# Car_board.net
KiCad netlist of a schematic drawn in Altium Designer
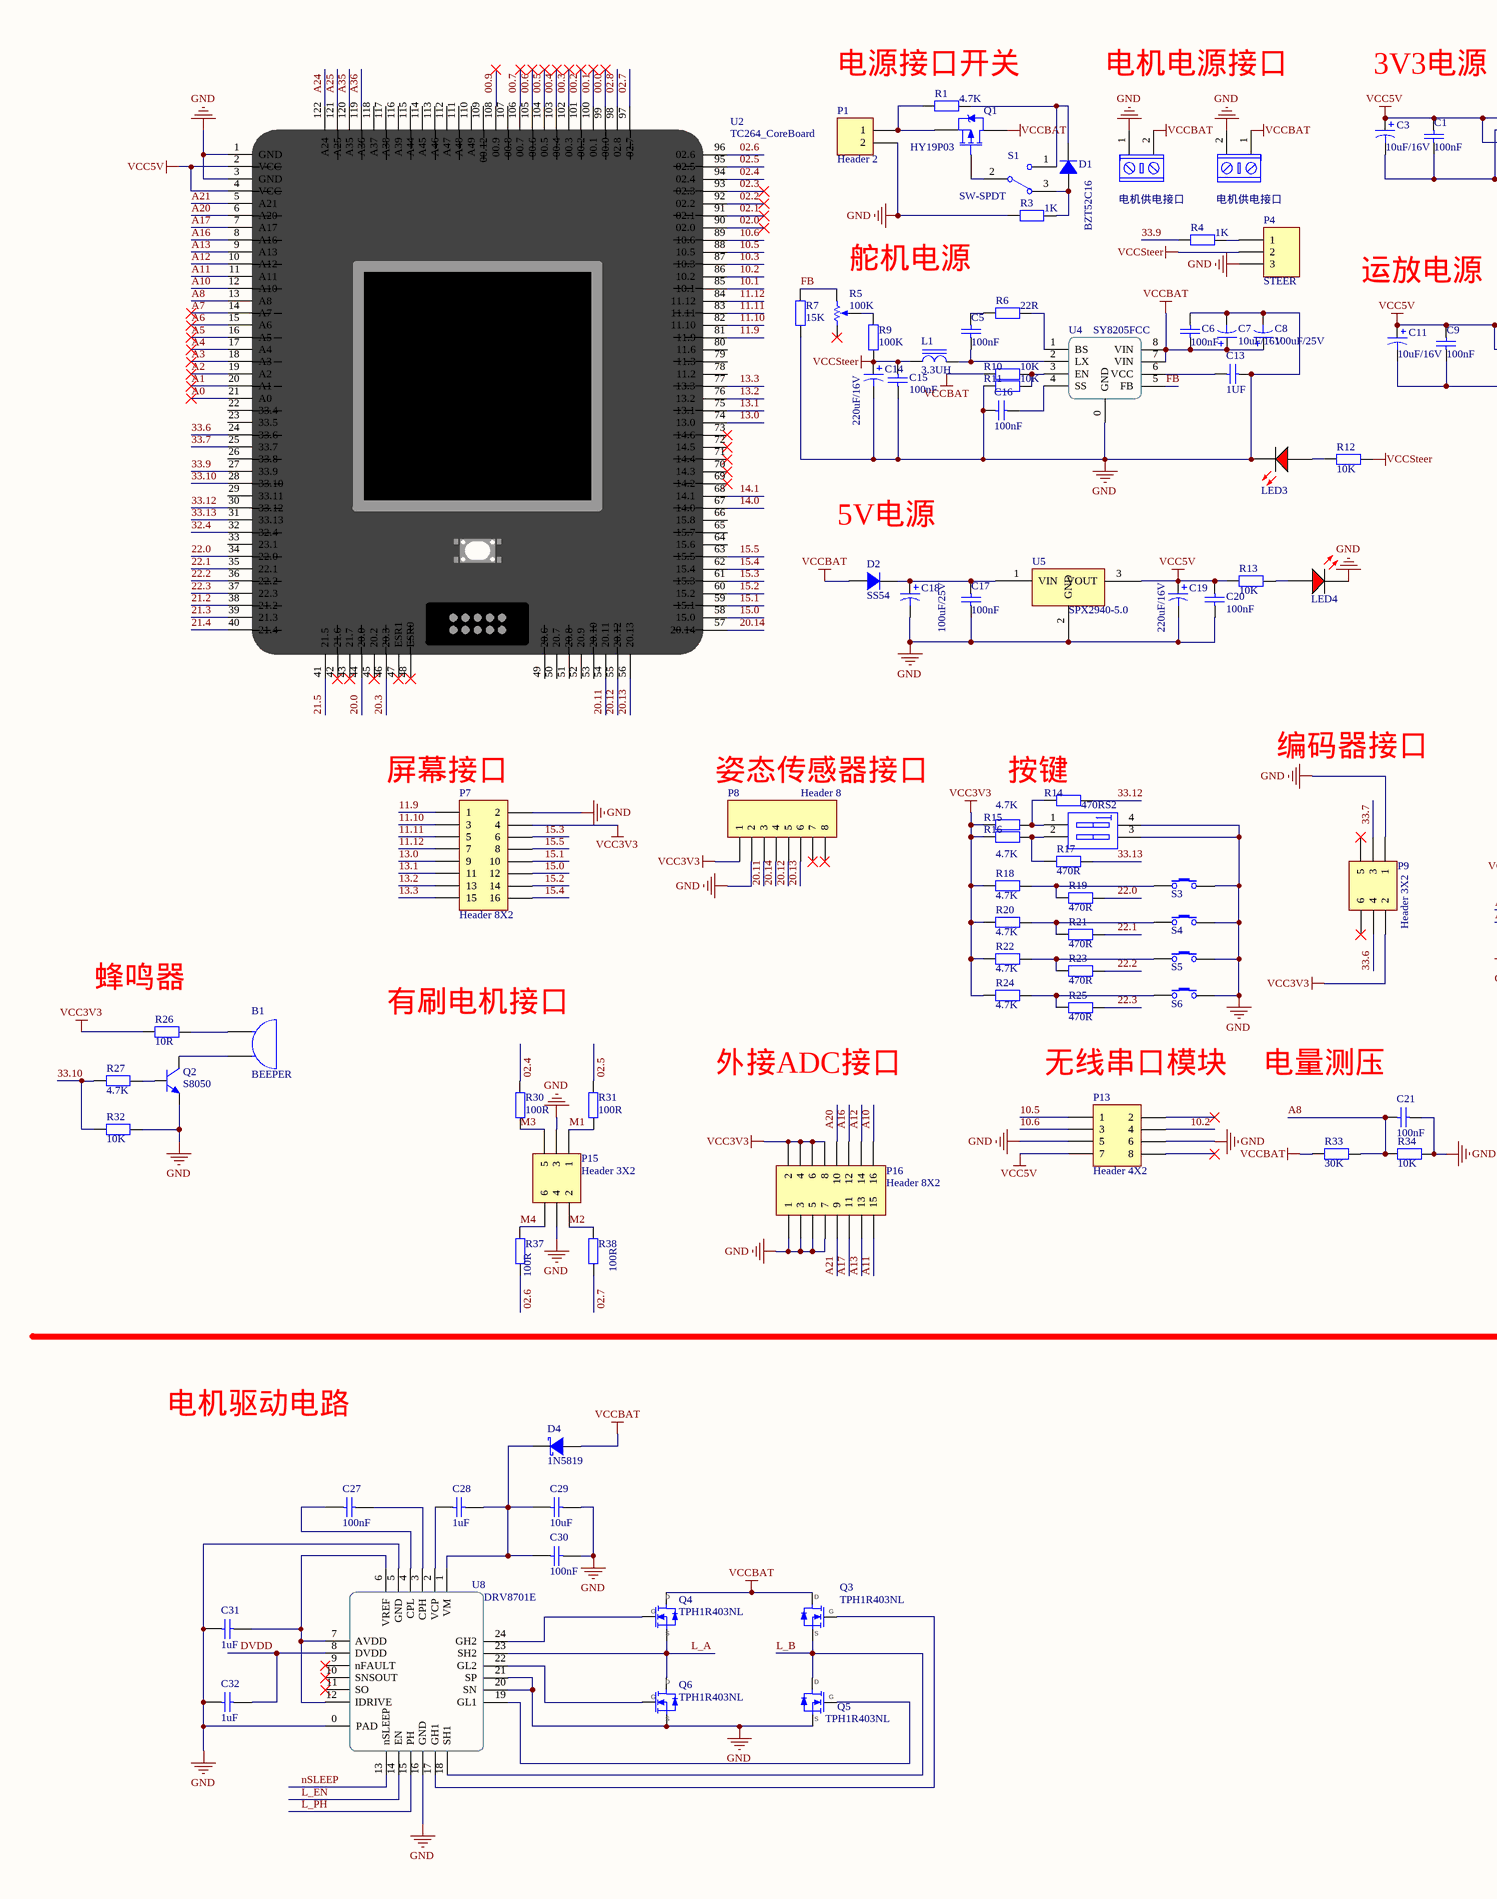
[diagram p0: Car_board.SchDoc, left]
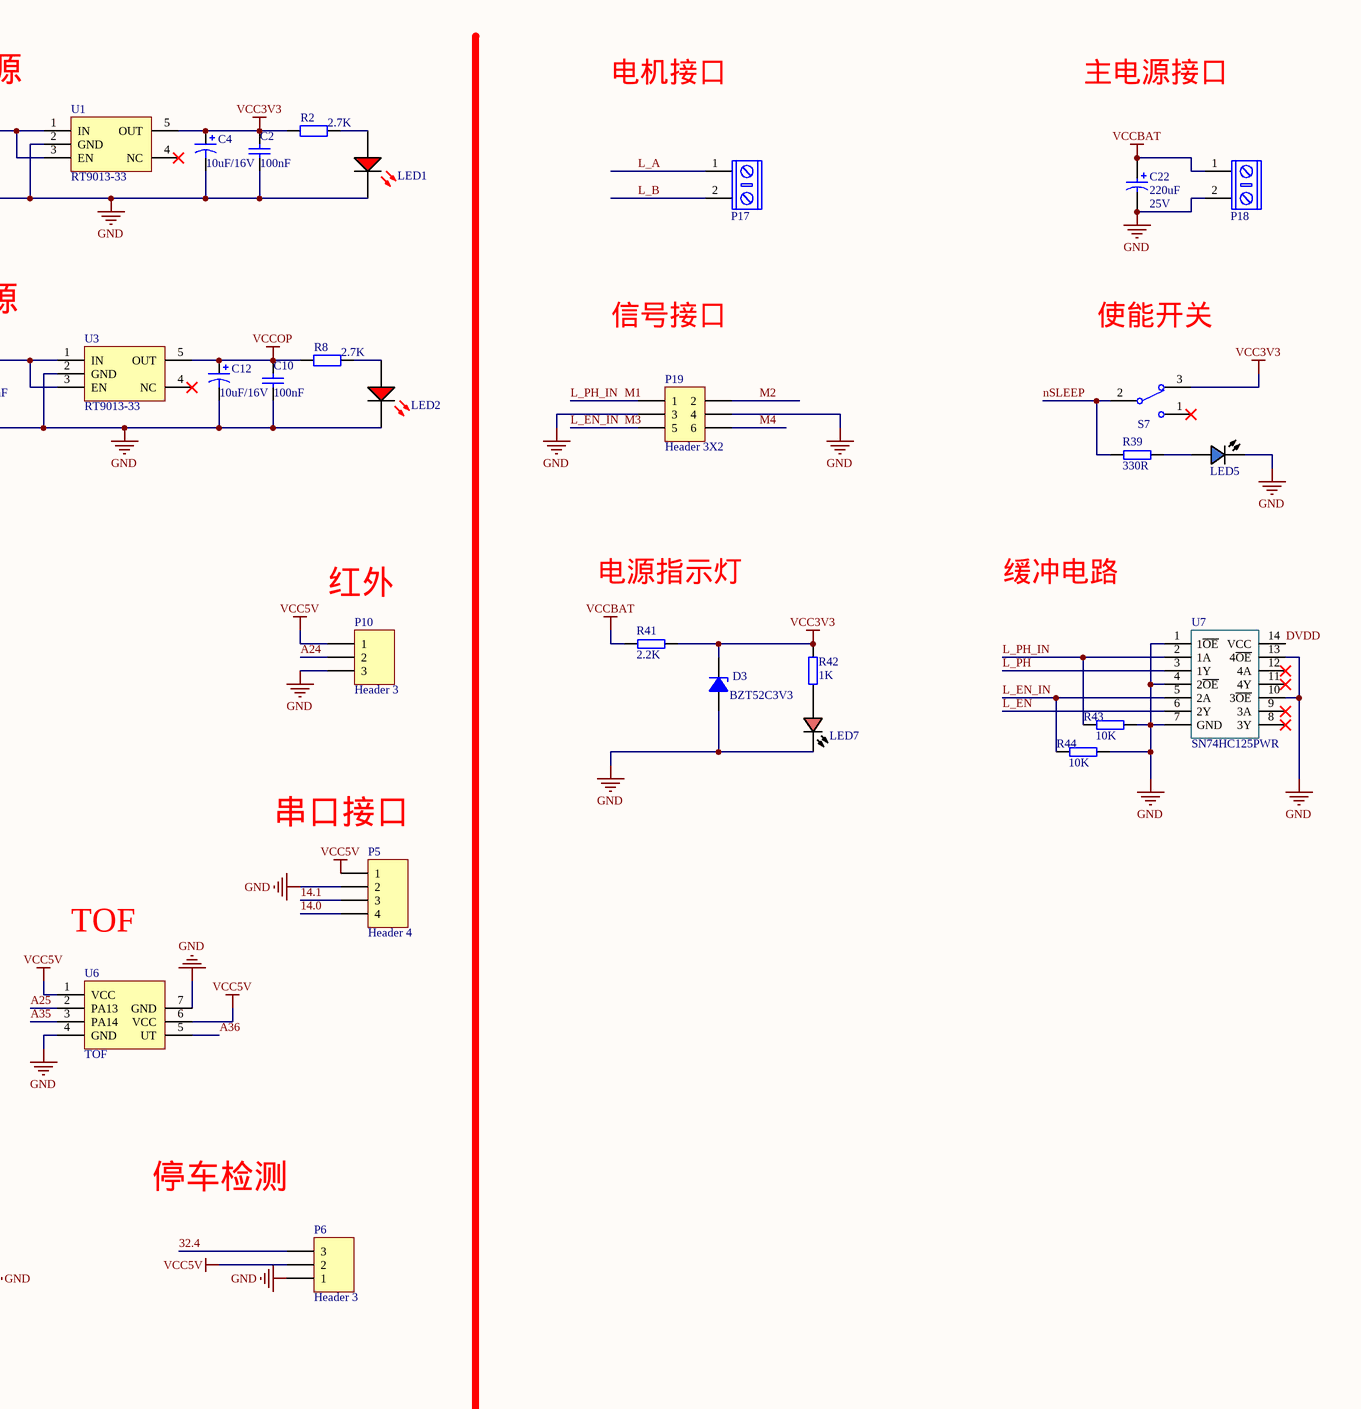
[diagram p1: Car_board.SchDoc, right]

(export (version "E")
  (design (tool "Eeschema 10.0.6"))
  (components
    (comp (ref "B1")
      (value "BEEPER")
      (footprint "BEEPER")
      (description "3V蜂鸣器")
      (libsource (lib "AMRP_XXX") (part "BUZZER"))
    )
    (comp (ref "C1")
      (value "100nF")
      (footprint "0603C")
      (description "电容")
      (fields (field (name "Comment") "Cap") (field (name "PUBLISHER") "Altium Limited"))
      (libsource (lib "AMRP_XXX") (part "Cap"))
    )
    (comp (ref "C2")
      (value "100nF")
      (footprint "0603C")
      (description "电容")
      (fields (field (name "Comment") "Cap") (field (name "PUBLISHER") "Altium Limited"))
      (libsource (lib "AMRP_XXX") (part "Cap"))
    )
    (comp (ref "C3")
      (value "10uF/16V")
      (footprint "3216")
      (description "钽电解电容/16V/A型封装")
      (fields (field (name "Comment") "Cap Pol2") (field (name "PUBLISHER") "Altium Limited"))
      (libsource (lib "AMRP_XXX") (part "Cap Pol2"))
    )
    (comp (ref "C4")
      (value "10uF/16V")
      (footprint "3216")
      (description "钽电解电容/16V/A型封装")
      (fields (field (name "Comment") "Cap Pol2") (field (name "PUBLISHER") "Altium Limited"))
      (libsource (lib "AMRP_XXX") (part "Cap Pol2"))
    )
    (comp (ref "C5")
      (value "100nF")
      (footprint "0603C")
      (description "电容")
      (fields (field (name "Comment") "Cap") (field (name "PUBLISHER") "Altium Limited"))
      (libsource (lib "AMRP_XXX") (part "Cap"))
    )
    (comp (ref "C6")
      (value "100nF")
      (footprint "0603C")
      (description "电容")
      (fields (field (name "Comment") "Cap") (field (name "PUBLISHER") "Altium Limited"))
      (libsource (lib "AMRP_XXX") (part "Cap"))
    )
    (comp (ref "C7")
      (value "10uF/16V")
      (footprint "3216")
      (description "钽电解电容/16V/A型封装")
      (fields (field (name "Comment") "Cap Pol2") (field (name "PUBLISHER") "Altium Limited"))
      (libsource (lib "AMRP_XXX") (part "Cap Pol2"))
    )
    (comp (ref "C8")
      (value "100uF/25V")
      (footprint "CAPSO_6.3*7.7")
      (description "钽电解电容/16V/A型封装")
      (fields (field (name "Comment") "Cap Pol2") (field (name "PUBLISHER") "Altium Limited"))
      (libsource (lib "AMRP_XXX") (part "Cap Pol2"))
    )
    (comp (ref "C9")
      (value "100nF")
      (footprint "0603C")
      (description "电容")
      (fields (field (name "Comment") "Cap") (field (name "PUBLISHER") "Altium Limited"))
      (libsource (lib "AMRP_XXX") (part "Cap"))
    )
    (comp (ref "C10")
      (value "100nF")
      (footprint "0603C")
      (description "电容")
      (fields (field (name "Comment") "Cap") (field (name "PUBLISHER") "Altium Limited"))
      (libsource (lib "AMRP_XXX") (part "Cap"))
    )
    (comp (ref "C11")
      (value "10uF/16V")
      (footprint "3216")
      (description "钽电解电容/16V/A型封装")
      (fields (field (name "Comment") "Cap Pol2") (field (name "PUBLISHER") "Altium Limited"))
      (libsource (lib "AMRP_XXX") (part "Cap Pol2"))
    )
    (comp (ref "C12")
      (value "10uF/16V")
      (footprint "3216")
      (description "钽电解电容/16V/A型封装")
      (fields (field (name "Comment") "Cap Pol2") (field (name "PUBLISHER") "Altium Limited"))
      (libsource (lib "AMRP_XXX") (part "Cap Pol2"))
    )
    (comp (ref "C13")
      (value "1UF")
      (footprint "0603C")
      (description "电容")
      (fields (field (name "Comment") "Cap") (field (name "PUBLISHER") "Altium Limited"))
      (libsource (lib "AMRP_XXX") (part "Cap"))
    )
    (comp (ref "C14")
      (value "220uF/16V")
      (footprint "CAPSO_6.3*7.7")
      (description "钽电解电容/16V/A型封装")
      (fields (field (name "Comment") "Cap Pol2") (field (name "PUBLISHER") "Altium Limited"))
      (libsource (lib "AMRP_XXX") (part "Cap Pol2"))
    )
    (comp (ref "C15")
      (value "100nF")
      (footprint "0603C")
      (description "电容")
      (fields (field (name "Comment") "Cap") (field (name "PUBLISHER") "Altium Limited"))
      (libsource (lib "AMRP_XXX") (part "Cap"))
    )
    (comp (ref "C16")
      (value "100nF")
      (footprint "0603C")
      (description "电容")
      (fields (field (name "Comment") "Cap") (field (name "PUBLISHER") "Altium Limited"))
      (libsource (lib "AMRP_XXX") (part "Cap"))
    )
    (comp (ref "C17")
      (value "100nF")
      (footprint "0603C")
      (description "电容")
      (fields (field (name "Comment") "Cap") (field (name "PUBLISHER") "Altium Limited"))
      (libsource (lib "AMRP_XXX") (part "Cap"))
    )
    (comp (ref "C18")
      (value "100uF/25V")
      (footprint "CAPSO_6.3*7.7")
      (description "钽电解电容/16V/A型封装")
      (fields (field (name "Comment") "Cap Pol2") (field (name "PUBLISHER") "Altium Limited"))
      (libsource (lib "AMRP_XXX") (part "Cap Pol2"))
    )
    (comp (ref "C19")
      (value "220uF/16V")
      (footprint "CAPSO_6.3*7.7")
      (description "钽电解电容/16V/A型封装")
      (fields (field (name "Comment") "Cap Pol2") (field (name "PUBLISHER") "Altium Limited"))
      (libsource (lib "AMRP_XXX") (part "Cap Pol2"))
    )
    (comp (ref "C20")
      (value "100nF")
      (footprint "0603C")
      (description "电容")
      (fields (field (name "Comment") "Cap") (field (name "PUBLISHER") "Altium Limited"))
      (libsource (lib "AMRP_XXX") (part "Cap"))
    )
    (comp (ref "C21")
      (value "100nF")
      (footprint "0603C")
      (description "电容")
      (fields (field (name "Comment") "Cap") (field (name "PUBLISHER") "Altium Limited"))
      (libsource (lib "AMRP_XXX") (part "Cap"))
    )
    (comp (ref "C22")
      (value "220uF")
      (footprint "CAPPR3.5-8X11.5")
      (description "Polarized Capacitor (Radial)")
      (fields
        (field (name "VOLTAGE") "25V")
        (field (name "Comment") "220uF 25V")
        (field (name "PUBLISHER") "Altium Limited")
      )
      (libsource (lib "DRV8701_DualMotorDriver") (part "Cap-Elect"))
    )
    (comp (ref "C27")
      (value "100nF")
      (footprint "CAPC1608[0603]S-N")
      (description "贴片电容")
      (fields
        (field (name "VOLTAGE") "50V")
        (field (name "TOLERANCE") "±10%")
        (field (name "PUBLISHER") "Altium Limited")
      )
      (libsource (lib "DRV8701_DualMotorDriver") (part "Cap-Chip_1"))
    )
    (comp (ref "C28")
      (value "1uF")
      (footprint "CAPC1608[0603]S-N")
      (description "贴片电容")
      (fields
        (field (name "VOLTAGE") "25V")
        (field (name "TOLERANCE") "±10%")
        (field (name "PUBLISHER") "Altium Limited")
      )
      (libsource (lib "DRV8701_DualMotorDriver") (part "Cap-Chip_2"))
    )
    (comp (ref "C29")
      (value "10uF")
      (footprint "CAPC2012[0805]S-N")
      (description "贴片电容")
      (fields
        (field (name "VOLTAGE") "25V")
        (field (name "TOLERANCE") "±10%")
        (field (name "PUBLISHER") "Altium Limited")
      )
      (libsource (lib "DRV8701_DualMotorDriver") (part "Cap-Chip"))
    )
    (comp (ref "C30")
      (value "100nF")
      (footprint "CAPC1608[0603]S-N")
      (description "贴片电容")
      (fields
        (field (name "VOLTAGE") "50V")
        (field (name "TOLERANCE") "±10%")
        (field (name "PUBLISHER") "Altium Limited")
      )
      (libsource (lib "DRV8701_DualMotorDriver") (part "Cap-Chip_1"))
    )
    (comp (ref "C31")
      (value "1uF")
      (footprint "CAPC1608[0603]S-N")
      (description "贴片电容")
      (fields
        (field (name "VOLTAGE") "25V")
        (field (name "TOLERANCE") "±10%")
        (field (name "PUBLISHER") "Altium Limited")
      )
      (libsource (lib "DRV8701_DualMotorDriver") (part "Cap-Chip_2"))
    )
    (comp (ref "C32")
      (value "1uF")
      (footprint "CAPC1608[0603]S-N")
      (description "贴片电容")
      (fields
        (field (name "VOLTAGE") "25V")
        (field (name "TOLERANCE") "±10%")
        (field (name "PUBLISHER") "Altium Limited")
      )
      (libsource (lib "DRV8701_DualMotorDriver") (part "Cap-Chip_2"))
    )
    (comp (ref "D1")
      (value "BZT52C16")
      (footprint "SOD-123")
      (description "TVS二极管 Diode")
      (fields (field (name "PUBLISHER") "Altium Limited"))
      (libsource (lib "TVS") (part "TVS"))
    )
    (comp (ref "D2")
      (value "SS54")
      (footprint "SOD-123")
      (description "TVS二极管 Diode")
      (fields (field (name "PUBLISHER") "Altium Limited"))
      (libsource (lib "TVS") (part "TVS"))
    )
    (comp (ref "D3")
      (value "BZT52C3V3")
      (footprint "SOD-123-L")
      (description "3.3V稳压二极管 SOD-123")
      (fields (field (name "PUBLISHER") "Altium Limited"))
      (libsource (lib "DRV8701_DualMotorDriver") (part "Diode Zen"))
    )
    (comp (ref "D4")
      (value "1N5819")
      (footprint "SOD-123-L")
      (description "肖特基二极管 Diode")
      (fields (field (name "PARTNUMBER") "1N5819") (field (name "PUBLISHER") "Altium Limited"))
      (libsource (lib "DRV8701_DualMotorDriver") (part "Diode Schottky"))
    )
    (comp (ref "L1")
      (value "3.3UH")
      (footprint "L-0630")
      (description "Power Inductor, Ferrite-Core")
      (fields (field (name "PUBLISHER") "Altium Limited"))
      (libsource (lib "工字电感") (part "Ind-Power"))
    )
    (comp (ref "LED1")
      (value "LED 3R")
      (footprint "0805D")
      (description "Red, Typical INFRARED GaAs LED")
      (fields (field (name "PUBLISHER") "Altium Limited"))
      (libsource (lib "直插LED5MM") (part "LED DIP Red"))
    )
    (comp (ref "LED2")
      (value "LED 3R")
      (footprint "0805D")
      (description "Red, Typical INFRARED GaAs LED")
      (fields (field (name "PUBLISHER") "Altium Limited"))
      (libsource (lib "直插LED5MM") (part "LED DIP Red"))
    )
    (comp (ref "LED3")
      (value "LED 3R")
      (footprint "0805D")
      (description "Red, Typical INFRARED GaAs LED")
      (fields (field (name "PUBLISHER") "Altium Limited"))
      (libsource (lib "直插LED5MM") (part "LED DIP Red"))
    )
    (comp (ref "LED4")
      (value "LED 3R")
      (footprint "0805D")
      (description "Red, Typical INFRARED GaAs LED")
      (fields (field (name "PUBLISHER") "Altium Limited"))
      (libsource (lib "直插LED5MM") (part "LED DIP Red"))
    )
    (comp (ref "LED5")
      (value "Blue")
      (footprint "LEDC1608(0603)")
      (description "Typical Chip LED")
      (fields (field (name "PUBLISHER") "Altium Limited"))
      (libsource (lib "DRV8701_DualMotorDriver") (part "LED Chip Blue"))
    )
    (comp (ref "LED7")
      (value "~")
      (footprint "LEDC1608(0603)")
      (description "Typical Chip LED")
      (fields (field (name "PUBLISHER") "Altium Limited"))
      (libsource (lib "DRV8701_DualMotorDriver") (part "LED Chip Red"))
    )
    (comp (ref "P1")
      (value "Header 2")
      (footprint "PCBComponent_1")
      (description "Header, 2-Pin")
      (fields (field (name "PUBLISHER") "Altium Limited"))
      (libsource (lib "Miscellaneous Connectors") (part "Header 2"))
    )
    (comp (ref "P2")
      (value "电机供电接口")
      (footprint "KF/WJ/DG 301-2p-5.0mm")
      (description "接线端子 2Pin")
      (libsource (lib "接线端子") (part "KF/WJ/DG 30x"))
    )
    (comp (ref "P3")
      (value "电机供电接口")
      (footprint "KF/WJ/DG 301-2p-5.0mm")
      (description "接线端子 2Pin")
      (libsource (lib "接线端子") (part "KF/WJ/DG 30x"))
    )
    (comp (ref "P4")
      (value "STEER")
      (footprint "HDR1X3")
      (description "Header, 3-Pin")
      (fields (field (name "PUBLISHER") "Altium Limited"))
      (libsource (lib "Miscellaneous Connectors") (part "Header 3"))
    )
    (comp (ref "P5")
      (value "Header 4")
      (footprint "HDR1X4")
      (description "Header, 4-Pin")
      (fields (field (name "PUBLISHER") "Altium Limited"))
      (libsource (lib "Miscellaneous Connectors") (part "Header 4"))
    )
    (comp (ref "P6")
      (value "Header 3")
      (footprint "HDR1X3")
      (description "Header, 3-Pin")
      (fields (field (name "PUBLISHER") "Altium Limited"))
      (libsource (lib "") (part "Header 3_1"))
    )
    (comp (ref "P7")
      (value "Header 8X2")
      (footprint "HDR2X8")
      (description "Header, 8-Pin, Dual row")
      (fields (field (name "PUBLISHER") "Altium Limited"))
      (libsource (lib "Miscellaneous Connectors") (part "Header 8X2"))
    )
    (comp (ref "P8")
      (value "Header 8")
      (footprint "HDR1X8")
      (description "Header, 8-Pin")
      (fields (field (name "PUBLISHER") "Altium Limited"))
      (libsource (lib "Miscellaneous Connectors") (part "Header 8"))
    )
    (comp (ref "P9")
      (value "Header 3X2")
      (footprint "HDR2X3")
      (description "Header, 3-Pin, Dual row")
      (fields (field (name "PUBLISHER") "Altium Limited"))
      (libsource (lib "Miscellaneous Connectors") (part "Header 3X2"))
    )
    (comp (ref "P10")
      (value "Header 3")
      (footprint "HDR1X3")
      (description "Header, 3-Pin")
      (fields (field (name "PUBLISHER") "Altium Limited"))
      (libsource (lib "Miscellaneous Connectors") (part "Header 3"))
    )
    (comp (ref "P13")
      (value "Header 4X2")
      (footprint "HDR2X4")
      (description "Header, 4-Pin, Dual row")
      (fields (field (name "PUBLISHER") "Altium Limited"))
      (libsource (lib "Miscellaneous Connectors") (part "Header 4X2"))
    )
    (comp (ref "P15")
      (value "Header 3X2")
      (footprint "HDR2X3")
      (description "Header, 3-Pin, Dual row")
      (fields (field (name "PUBLISHER") "Altium Limited"))
      (libsource (lib "Miscellaneous Connectors") (part "Header 3X2"))
    )
    (comp (ref "P16")
      (value "Header 8X2")
      (footprint "HDR2X8")
      (description "Header, 8-Pin, Dual row")
      (fields (field (name "PUBLISHER") "Altium Limited"))
      (libsource (lib "") (part "Header 8X2_1"))
    )
    (comp (ref "P17")
      (value "KF/WJ/DG 30x connecter")
      (footprint "KF/WJ/DG 301-2p-5.0mm")
      (description "接线端子 2Pin")
      (libsource (lib "DRV8701_DualMotorDriver") (part "KF/WJ/DG 30x"))
    )
    (comp (ref "P18")
      (value "KF/WJ/DG 30x connecter")
      (footprint "KF/WJ/DG 301-2p-5.0mm")
      (description "接线端子 2Pin")
      (libsource (lib "DRV8701_DualMotorDriver") (part "KF/WJ/DG 30x"))
    )
    (comp (ref "P19")
      (value "Header 3X2")
      (footprint "HDR2X3")
      (description "Header, 3-Pin, Dual row")
      (fields (field (name "PUBLISHER") "Altium Limited"))
      (libsource (lib "DRV8701_DualMotorDriver") (part "Header 3X2"))
    )
    (comp (ref "Q1")
      (value "HY19P03")
      (footprint "TO-252")
      (description "P-Channel Power MOSFET")
      (fields (field (name "PUBLISHER") "Altium Limited"))
      (libsource (lib "Miscellaneous Devices") (part "PMOS-2"))
    )
    (comp (ref "Q2")
      (value "S8050")
      (footprint "SOT-23")
      (description "Discrete NPN Bipolar Transistor")
      (fields (field (name "PARTNUMBER") "S8050") (field (name "PUBLISHER") "Altium Limited"))
      (libsource (lib "S8050") (part "NPN S8050"))
    )
    (comp (ref "Q3")
      (value "TPH1R403NL")
      (footprint "DFN5x6")
      (description "东芝 N沟 MOS")
      (libsource (lib "DRV8701_DualMotorDriver") (part "TPH1R403NL"))
    )
    (comp (ref "Q4")
      (value "TPH1R403NL")
      (footprint "DFN5x6")
      (description "东芝 N沟 MOS")
      (libsource (lib "DRV8701_DualMotorDriver") (part "TPH1R403NL"))
    )
    (comp (ref "Q5")
      (value "TPH1R403NL")
      (footprint "DFN5x6")
      (description "东芝 N沟 MOS")
      (libsource (lib "DRV8701_DualMotorDriver") (part "TPH1R403NL"))
    )
    (comp (ref "Q6")
      (value "TPH1R403NL")
      (footprint "DFN5x6")
      (description "东芝 N沟 MOS")
      (libsource (lib "DRV8701_DualMotorDriver") (part "TPH1R403NL"))
    )
    (comp (ref "R1")
      (value "4.7K")
      (footprint "0603R")
      (description "电阻")
      (fields (field (name "Comment") "Res2") (field (name "PUBLISHER") "Altium Limited"))
      (libsource (lib "") (part "Res2_2"))
    )
    (comp (ref "R2")
      (value "2.7K")
      (footprint "0603R")
      (description "电阻")
      (fields (field (name "Comment") "Res2") (field (name "PUBLISHER") "Altium Limited"))
      (libsource (lib "AMRP_XXX") (part "Res2"))
    )
    (comp (ref "R3")
      (value "1K")
      (footprint "0603R")
      (description "电阻")
      (fields (field (name "Comment") "Res2") (field (name "PUBLISHER") "Altium Limited"))
      (libsource (lib "") (part "Res2_2"))
    )
    (comp (ref "R4")
      (value "1K")
      (footprint "0603R")
      (description "电阻")
      (fields (field (name "Comment") "Res2") (field (name "PUBLISHER") "Altium Limited"))
      (libsource (lib "AMRP_XXX") (part "Res2"))
    )
    (comp (ref "R5")
      (value "100K")
      (footprint "VR5_N")
      (description "精密电位器")
      (fields (field (name "Comment") "RPot") (field (name "PUBLISHER") "Altium Limited"))
      (libsource (lib "AMRP_XXX") (part "RPot"))
    )
    (comp (ref "R6")
      (value "22R")
      (footprint "0603R")
      (description "电阻")
      (fields (field (name "Comment") "Res2") (field (name "PUBLISHER") "Altium Limited"))
      (libsource (lib "AMRP_XXX") (part "Res2"))
    )
    (comp (ref "R7")
      (value "15K")
      (footprint "0603R")
      (description "电阻")
      (fields (field (name "Comment") "Res2") (field (name "PUBLISHER") "Altium Limited"))
      (libsource (lib "") (part "Res2_3"))
    )
    (comp (ref "R8")
      (value "2.7K")
      (footprint "0603R")
      (description "电阻")
      (fields (field (name "Comment") "Res2") (field (name "PUBLISHER") "Altium Limited"))
      (libsource (lib "AMRP_XXX") (part "Res2"))
    )
    (comp (ref "R9")
      (value "100K")
      (footprint "0603R")
      (description "电阻")
      (fields (field (name "Comment") "Res2") (field (name "PUBLISHER") "Altium Limited"))
      (libsource (lib "") (part "Res2_3"))
    )
    (comp (ref "R10")
      (value "10K")
      (footprint "0603R")
      (description "电阻")
      (fields (field (name "Comment") "Res2") (field (name "PUBLISHER") "Altium Limited"))
      (libsource (lib "AMRP_XXX") (part "Res2"))
    )
    (comp (ref "R11")
      (value "10K")
      (footprint "0603R")
      (description "电阻")
      (fields (field (name "Comment") "Res2") (field (name "PUBLISHER") "Altium Limited"))
      (libsource (lib "AMRP_XXX") (part "Res2"))
    )
    (comp (ref "R12")
      (value "10K")
      (footprint "0603R")
      (description "电阻")
      (fields (field (name "Comment") "Res2") (field (name "PUBLISHER") "Altium Limited"))
      (libsource (lib "AMRP_XXX") (part "Res2"))
    )
    (comp (ref "R13")
      (value "10K")
      (footprint "0603R")
      (description "电阻")
      (fields (field (name "Comment") "Res2") (field (name "PUBLISHER") "Altium Limited"))
      (libsource (lib "") (part "Res2_2"))
    )
    (comp (ref "R14")
      (value "470R")
      (footprint "0603R")
      (description "电阻")
      (fields (field (name "Comment") "Res2") (field (name "PUBLISHER") "Altium Limited"))
      (libsource (lib "") (part "Res2_2"))
    )
    (comp (ref "R15")
      (value "4.7K")
      (footprint "0603R")
      (description "电阻")
      (fields (field (name "Comment") "Res2") (field (name "PUBLISHER") "Altium Limited"))
      (libsource (lib "") (part "Res2_2"))
    )
    (comp (ref "R16")
      (value "4.7K")
      (footprint "0603R")
      (description "电阻")
      (fields (field (name "Comment") "Res2") (field (name "PUBLISHER") "Altium Limited"))
      (libsource (lib "") (part "Res2_2"))
    )
    (comp (ref "R17")
      (value "470R")
      (footprint "0603R")
      (description "电阻")
      (fields (field (name "Comment") "Res2") (field (name "PUBLISHER") "Altium Limited"))
      (libsource (lib "") (part "Res2_2"))
    )
    (comp (ref "R18")
      (value "4.7K")
      (footprint "0603R")
      (description "电阻")
      (fields (field (name "Comment") "Res2") (field (name "PUBLISHER") "Altium Limited"))
      (libsource (lib "") (part "Res2_2"))
    )
    (comp (ref "R19")
      (value "470R")
      (footprint "0603R")
      (description "电阻")
      (fields (field (name "Comment") "Res2") (field (name "PUBLISHER") "Altium Limited"))
      (libsource (lib "") (part "Res2_2"))
    )
    (comp (ref "R20")
      (value "4.7K")
      (footprint "0603R")
      (description "电阻")
      (fields (field (name "Comment") "Res2") (field (name "PUBLISHER") "Altium Limited"))
      (libsource (lib "") (part "Res2_2"))
    )
    (comp (ref "R21")
      (value "470R")
      (footprint "0603R")
      (description "电阻")
      (fields (field (name "Comment") "Res2") (field (name "PUBLISHER") "Altium Limited"))
      (libsource (lib "") (part "Res2_2"))
    )
    (comp (ref "R22")
      (value "4.7K")
      (footprint "0603R")
      (description "电阻")
      (fields (field (name "Comment") "Res2") (field (name "PUBLISHER") "Altium Limited"))
      (libsource (lib "") (part "Res2_2"))
    )
    (comp (ref "R23")
      (value "470R")
      (footprint "0603R")
      (description "电阻")
      (fields (field (name "Comment") "Res2") (field (name "PUBLISHER") "Altium Limited"))
      (libsource (lib "") (part "Res2_2"))
    )
    (comp (ref "R24")
      (value "4.7K")
      (footprint "0603R")
      (description "电阻")
      (fields (field (name "Comment") "Res2") (field (name "PUBLISHER") "Altium Limited"))
      (libsource (lib "") (part "Res2_2"))
    )
    (comp (ref "R25")
      (value "470R")
      (footprint "0603R")
      (description "电阻")
      (fields (field (name "Comment") "Res2") (field (name "PUBLISHER") "Altium Limited"))
      (libsource (lib "") (part "Res2_2"))
    )
    (comp (ref "R26")
      (value "10R")
      (footprint "0603R")
      (description "电阻")
      (fields (field (name "Comment") "Res2") (field (name "PUBLISHER") "Altium Limited"))
      (libsource (lib "") (part "Res2_2"))
    )
    (comp (ref "R27")
      (value "4.7K")
      (footprint "0603R")
      (description "电阻")
      (fields (field (name "Comment") "Res2") (field (name "PUBLISHER") "Altium Limited"))
      (libsource (lib "") (part "Res2_2"))
    )
    (comp (ref "R30")
      (value "100R")
      (footprint "0603R")
      (description "电阻")
      (fields (field (name "Comment") "Res2") (field (name "PUBLISHER") "Altium Limited"))
      (libsource (lib "") (part "Res2_1"))
    )
    (comp (ref "R31")
      (value "100R")
      (footprint "0603R")
      (description "电阻")
      (fields (field (name "Comment") "Res2") (field (name "PUBLISHER") "Altium Limited"))
      (libsource (lib "") (part "Res2_1"))
    )
    (comp (ref "R32")
      (value "10K")
      (footprint "0603R")
      (description "电阻")
      (fields (field (name "Comment") "Res2") (field (name "PUBLISHER") "Altium Limited"))
      (libsource (lib "") (part "Res2_2"))
    )
    (comp (ref "R33")
      (value "30K")
      (footprint "0603R")
      (description "电阻")
      (fields (field (name "Comment") "Res2") (field (name "PUBLISHER") "Altium Limited"))
      (libsource (lib "") (part "Res2_2"))
    )
    (comp (ref "R34")
      (value "10K")
      (footprint "0603R")
      (description "电阻")
      (fields (field (name "Comment") "Res2") (field (name "PUBLISHER") "Altium Limited"))
      (libsource (lib "") (part "Res2_2"))
    )
    (comp (ref "R37")
      (value "100R")
      (footprint "0603R")
      (description "电阻")
      (fields (field (name "Comment") "Res2") (field (name "PUBLISHER") "Altium Limited"))
      (libsource (lib "") (part "Res2_1"))
    )
    (comp (ref "R38")
      (value "100R")
      (footprint "0603R")
      (description "电阻")
      (fields (field (name "Comment") "Res2") (field (name "PUBLISHER") "Altium Limited"))
      (libsource (lib "") (part "Res2_1"))
    )
    (comp (ref "R39")
      (value "330R")
      (footprint "RESC1608[0603]S-N")
      (description "贴片电阻")
      (fields
        (field (name "TOLERANCE") "±1%")
        (field (name "Comment") "330R ±1%")
        (field (name "PUBLISHER") "Altium Limited")
      )
      (libsource (lib "DRV8701_DualMotorDriver") (part "Res-Chip_3"))
    )
    (comp (ref "R41")
      (value "2.2K")
      (footprint "RESC1608[0603]S-N")
      (description "贴片电阻")
      (fields
        (field (name "TOLERANCE") "±1%")
        (field (name "Comment") "2.2K ±1%")
        (field (name "PUBLISHER") "Altium Limited")
      )
      (libsource (lib "DRV8701_DualMotorDriver") (part "Res-Chip"))
    )
    (comp (ref "R42")
      (value "1K")
      (footprint "RESC1608[0603]S-N")
      (description "贴片电阻")
      (fields
        (field (name "TOLERANCE") "±1%")
        (field (name "Comment") "1K ±1%")
        (field (name "PUBLISHER") "Altium Limited")
      )
      (libsource (lib "DRV8701_DualMotorDriver") (part "Res-Chip_2"))
    )
    (comp (ref "R43")
      (value "10K")
      (footprint "RESC1608[0603]S-N")
      (description "贴片电阻")
      (fields
        (field (name "TOLERANCE") "±1%")
        (field (name "Comment") "10K ±1%")
        (field (name "PUBLISHER") "Altium Limited")
      )
      (libsource (lib "DRV8701_DualMotorDriver") (part "Res-Chip_1"))
    )
    (comp (ref "R44")
      (value "10K")
      (footprint "RESC1608[0603]S-N")
      (description "贴片电阻")
      (fields
        (field (name "TOLERANCE") "±1%")
        (field (name "Comment") "10K ±1%")
        (field (name "PUBLISHER") "Altium Limited")
      )
      (libsource (lib "DRV8701_DualMotorDriver") (part "Res-Chip_1"))
    )
    (comp (ref "S1")
      (value "SW-SPDT")
      (footprint "扭子开关102 - 2")
      (description "SPDT Subminiature Toggle Switch, Right Angle Mounting, Vertical Actuation")
      (fields (field (name "PUBLISHER") "Altium Limited"))
      (libsource (lib "Miscellaneous Devices") (part "SW-SPDT"))
    )
    (comp (ref "S2")
      (value "SW DIP-2")
      (footprint "DIP4")
      (description "2位拨码开关")
      (fields (field (name "PUBLISHER") "Altium Limited"))
      (libsource (lib "拨码开关") (part "Code SW-2"))
    )
    (comp (ref "S3")
      (value "Button")
      (footprint "KEY-2-SMD-3*6")
      (description "按键")
      (fields (field (name "PUBLISHER") "Altium Limited"))
      (libsource (lib "按键") (part "KEY"))
    )
    (comp (ref "S4")
      (value "Button")
      (footprint "KEY-2-SMD-3*6")
      (description "按键")
      (fields (field (name "PUBLISHER") "Altium Limited"))
      (libsource (lib "按键") (part "KEY"))
    )
    (comp (ref "S5")
      (value "Button")
      (footprint "KEY-2-SMD-3*6")
      (description "按键")
      (fields (field (name "PUBLISHER") "Altium Limited"))
      (libsource (lib "按键") (part "KEY"))
    )
    (comp (ref "S6")
      (value "Button")
      (footprint "KEY-2-SMD-3*6")
      (description "按键")
      (fields (field (name "PUBLISHER") "Altium Limited"))
      (libsource (lib "按键") (part "KEY"))
    )
    (comp (ref "S7")
      (value "SW-SPDT")
      (footprint "SS12D10")
      (description "单刀双掷开关 3脚船型、钮子、拨动开关 SPDT Subminiature Toggle Switch")
      (fields (field (name "PUBLISHER") "Altium Limited"))
      (libsource (lib "DRV8701_DualMotorDriver") (part "SW-SPDT"))
    )
    (comp (ref "U1")
      (value "RT9013-33")
      (footprint "SOT-23-5")
      (description "3.3V 500mA SOT-23-5 LDO")
      (libsource (lib "RT9013") (part "RT9013-33"))
    )
    (comp (ref "U2")
      (value "TC264_CoreBoard")
      (footprint "TC264_CoreBoard")
      (description "逐飞科技TC264核心板")
      (libsource (lib "TC264_CoreBoard") (part "TC264_CoreBoard"))
    )
    (comp (ref "U3")
      (value "RT9013-33")
      (footprint "SOT-23-5")
      (description "3.3V 500mA SOT-23-5 LDO")
      (libsource (lib "RT9013") (part "RT9013-33"))
    )
    (comp (ref "U4")
      (value "SY8205FCC")
      (footprint "SOP-8E")
      (description "同步buck")
      (libsource (lib "SY8205FCC") (part "SY8205FCC"))
    )
    (comp (ref "U5")
      (value "SPX2940-5.0")
      (footprint "TO-263-3")
      (description "SPX2940-5.0 5V LDO TO-263-3")
      (libsource (lib "SPX2940-5.0") (part "SPX2940-5.0"))
    )
    (comp (ref "U6") (value "TOF") (footprint "TOF") (libsource (lib "DRV8701_DualMotorDriver") (part "TOF")))
    (comp (ref "U7")
      (value "SN74HC125PWR")
      (footprint "TSSOP-14")
      (description "三态输出的四路缓冲器 TSSOP-20")
      (libsource (lib "DRV8701_DualMotorDriver") (part "SN74HC125PWR"))
    )
    (comp (ref "U8")
      (value "DRV8701E")
      (footprint "QFN24-4x4")
      (description "DRV8701E Ti全桥驱动芯片")
      (libsource (lib "DRV8701_DualMotorDriver") (part "DRV8701E"))
    )
  )
  (nets
    (net (code "1") (name "/00.0") (class "Default")
      (node (ref "U2") (pin "99") (pinfunction "00.0_99") (pintype "passive+no_connect"))
    )
    (net (code "2") (name "/00.1") (class "Default")
      (node (ref "U2") (pin "100") (pinfunction "00.1_100") (pintype "passive+no_connect"))
    )
    (net (code "3") (name "/00.2") (class "Default")
      (node (ref "U2") (pin "101") (pinfunction "00.2_101") (pintype "passive+no_connect"))
    )
    (net (code "4") (name "/00.3") (class "Default")
      (node (ref "U2") (pin "102") (pinfunction "00.3_102") (pintype "passive+no_connect"))
    )
    (net (code "5") (name "/00.4") (class "Default")
      (node (ref "U2") (pin "103") (pinfunction "00.4_103") (pintype "passive+no_connect"))
    )
    (net (code "6") (name "/00.5") (class "Default")
      (node (ref "U2") (pin "104") (pinfunction "00.5_104") (pintype "passive+no_connect"))
    )
    (net (code "7") (name "/00.6") (class "Default")
      (node (ref "U2") (pin "105") (pinfunction "00.6_105") (pintype "passive+no_connect"))
    )
    (net (code "8") (name "/00.7") (class "Default")
      (node (ref "U2") (pin "106") (pinfunction "00.7_106") (pintype "passive+no_connect"))
    )
    (net (code "9") (name "/00.9") (class "Default")
      (node (ref "U2") (pin "108") (pinfunction "00.9_108") (pintype "passive+no_connect"))
    )
    (net (code "10") (name "/02.0") (class "Default")
      (node (ref "U2") (pin "90") (pinfunction "02.0_90") (pintype "passive+no_connect"))
    )
    (net (code "11") (name "/02.1") (class "Default")
      (node (ref "U2") (pin "91") (pinfunction "02.1_91") (pintype "passive+no_connect"))
    )
    (net (code "12") (name "/02.2") (class "Default")
      (node (ref "U2") (pin "92") (pinfunction "02.2_92") (pintype "passive+no_connect"))
    )
    (net (code "13") (name "/02.3") (class "Default")
      (node (ref "U2") (pin "93") (pinfunction "02.3_93") (pintype "passive+no_connect"))
    )
    (net (code "14") (name "/02.4") (class "Default")
      (node (ref "R30") (pin "1") (pinfunction "1_1") (pintype "passive"))
      (node (ref "U2") (pin "94") (pinfunction "02.4_94") (pintype "passive"))
    )
    (net (code "15") (name "/02.5") (class "Default")
      (node (ref "R31") (pin "1") (pinfunction "1_1") (pintype "passive"))
      (node (ref "U2") (pin "95") (pinfunction "02.5_95") (pintype "passive"))
    )
    (net (code "16") (name "/02.6") (class "Default")
      (node (ref "R37") (pin "2") (pinfunction "2_2") (pintype "passive"))
      (node (ref "U2") (pin "96") (pinfunction "02.6_96") (pintype "passive"))
    )
    (net (code "17") (name "/02.7") (class "Default")
      (node (ref "R38") (pin "2") (pinfunction "2_2") (pintype "passive"))
      (node (ref "U2") (pin "97") (pinfunction "02.7_97") (pintype "passive"))
    )
    (net (code "18") (name "/02.8") (class "Default")
      (node (ref "U2") (pin "98") (pinfunction "02.8_98") (pintype "passive"))
    )
    (net (code "19") (name "/10.1") (class "Default")
      (node (ref "U2") (pin "85") (pinfunction "10.1_85") (pintype "passive"))
    )
    (net (code "20") (name "/10.2") (class "Default")
      (node (ref "P13") (pin "4") (pinfunction "4_4") (pintype "passive"))
      (node (ref "U2") (pin "86") (pinfunction "10.2_86") (pintype "passive"))
    )
    (net (code "21") (name "/10.3") (class "Default")
      (node (ref "U2") (pin "87") (pinfunction "10.3_87") (pintype "passive"))
    )
    (net (code "22") (name "/10.5") (class "Default")
      (node (ref "P13") (pin "1") (pinfunction "1_1") (pintype "passive"))
      (node (ref "U2") (pin "88") (pinfunction "10.5_88") (pintype "passive"))
    )
    (net (code "23") (name "/10.6") (class "Default")
      (node (ref "P13") (pin "3") (pinfunction "3_3") (pintype "passive"))
      (node (ref "U2") (pin "89") (pinfunction "10.6_89") (pintype "passive"))
    )
    (net (code "24") (name "/11.9") (class "Default")
      (node (ref "P7") (pin "1") (pinfunction "1_1") (pintype "passive"))
      (node (ref "U2") (pin "81") (pinfunction "11.9_81") (pintype "passive"))
    )
    (net (code "25") (name "/11.10") (class "Default")
      (node (ref "P7") (pin "3") (pinfunction "3_3") (pintype "passive"))
      (node (ref "U2") (pin "82") (pinfunction "11.10_82") (pintype "passive"))
    )
    (net (code "26") (name "/11.11") (class "Default")
      (node (ref "P7") (pin "5") (pinfunction "5_5") (pintype "passive"))
      (node (ref "U2") (pin "83") (pinfunction "11.11_83") (pintype "passive"))
    )
    (net (code "27") (name "/11.12") (class "Default")
      (node (ref "P7") (pin "7") (pinfunction "7_7") (pintype "passive"))
      (node (ref "U2") (pin "84") (pinfunction "11.12_84") (pintype "passive"))
    )
    (net (code "28") (name "/13.0") (class "Default")
      (node (ref "P7") (pin "9") (pinfunction "9_9") (pintype "passive"))
      (node (ref "U2") (pin "74") (pinfunction "13.0_74") (pintype "passive"))
    )
    (net (code "29") (name "/13.1") (class "Default")
      (node (ref "P7") (pin "11") (pinfunction "11_11") (pintype "passive"))
      (node (ref "U2") (pin "75") (pinfunction "13.1_75") (pintype "passive"))
    )
    (net (code "30") (name "/13.2") (class "Default")
      (node (ref "P7") (pin "13") (pinfunction "13_13") (pintype "passive"))
      (node (ref "U2") (pin "76") (pinfunction "13.2_76") (pintype "passive"))
    )
    (net (code "31") (name "/13.3") (class "Default")
      (node (ref "P7") (pin "15") (pinfunction "15_15") (pintype "passive"))
      (node (ref "U2") (pin "77") (pinfunction "13.3_77") (pintype "passive"))
    )
    (net (code "32") (name "/14.0") (class "Default")
      (node (ref "P5") (pin "4") (pinfunction "4_4") (pintype "passive"))
      (node (ref "U2") (pin "67") (pinfunction "14.0_67") (pintype "passive"))
    )
    (net (code "33") (name "/14.1") (class "Default")
      (node (ref "P5") (pin "3") (pinfunction "3_3") (pintype "passive"))
      (node (ref "U2") (pin "68") (pinfunction "14.1_68") (pintype "passive"))
    )
    (net (code "34") (name "/15.0") (class "Default")
      (node (ref "P7") (pin "12") (pinfunction "12_12") (pintype "passive"))
      (node (ref "U2") (pin "58") (pinfunction "15.0_58") (pintype "passive"))
    )
    (net (code "35") (name "/15.1") (class "Default")
      (node (ref "P7") (pin "10") (pinfunction "10_10") (pintype "passive"))
      (node (ref "U2") (pin "59") (pinfunction "15.1_59") (pintype "passive"))
    )
    (net (code "36") (name "/15.2") (class "Default")
      (node (ref "P7") (pin "14") (pinfunction "14_14") (pintype "passive"))
      (node (ref "U2") (pin "60") (pinfunction "15.2_60") (pintype "passive"))
    )
    (net (code "37") (name "/15.3") (class "Default")
      (node (ref "P7") (pin "6") (pinfunction "6_6") (pintype "passive"))
      (node (ref "U2") (pin "61") (pinfunction "15.3_61") (pintype "passive"))
    )
    (net (code "38") (name "/15.4") (class "Default")
      (node (ref "P7") (pin "16") (pinfunction "16_16") (pintype "passive"))
      (node (ref "U2") (pin "62") (pinfunction "15.4_62") (pintype "passive"))
    )
    (net (code "39") (name "/15.5") (class "Default")
      (node (ref "P7") (pin "8") (pinfunction "8_8") (pintype "passive"))
      (node (ref "U2") (pin "63") (pinfunction "15.5_63") (pintype "passive"))
    )
    (net (code "40") (name "/20.0") (class "Default")
      (node (ref "U2") (pin "44") (pinfunction "20.0_44") (pintype "passive"))
    )
    (net (code "41") (name "/20.3") (class "Default")
      (node (ref "U2") (pin "46") (pinfunction "20.3_46") (pintype "passive"))
    )
    (net (code "42") (name "/20.11") (class "Default")
      (node (ref "P8") (pin "3") (pinfunction "3_3") (pintype "passive"))
      (node (ref "U2") (pin "54") (pinfunction "20.11_54") (pintype "passive"))
    )
    (net (code "43") (name "/20.12") (class "Default")
      (node (ref "P8") (pin "5") (pinfunction "5_5") (pintype "passive"))
      (node (ref "U2") (pin "55") (pinfunction "20.12_55") (pintype "passive"))
    )
    (net (code "44") (name "/20.13") (class "Default")
      (node (ref "P8") (pin "6") (pinfunction "6_6") (pintype "passive"))
      (node (ref "U2") (pin "56") (pinfunction "20.13_56") (pintype "passive"))
    )
    (net (code "45") (name "/20.14") (class "Default")
      (node (ref "P8") (pin "4") (pinfunction "4_4") (pintype "passive"))
      (node (ref "U2") (pin "57") (pinfunction "20.14_57") (pintype "passive"))
    )
    (net (code "46") (name "/21.2") (class "Default")
      (node (ref "U2") (pin "38") (pinfunction "21.2_38") (pintype "passive"))
    )
    (net (code "47") (name "/21.3") (class "Default")
      (node (ref "U2") (pin "39") (pinfunction "21.3_39") (pintype "passive"))
    )
    (net (code "48") (name "/21.4") (class "Default")
      (node (ref "U2") (pin "40") (pinfunction "21.4_40") (pintype "passive"))
    )
    (net (code "49") (name "/21.5") (class "Default")
      (node (ref "U2") (pin "41") (pinfunction "21.5_41") (pintype "passive"))
    )
    (net (code "50") (name "/22.0") (class "Default")
      (node (ref "R19") (pin "1") (pinfunction "1_1") (pintype "passive"))
      (node (ref "U2") (pin "34") (pinfunction "22.0_34") (pintype "passive"))
    )
    (net (code "51") (name "/22.1") (class "Default")
      (node (ref "R21") (pin "1") (pinfunction "1_1") (pintype "passive"))
      (node (ref "U2") (pin "35") (pinfunction "22.1_35") (pintype "passive"))
    )
    (net (code "52") (name "/22.2") (class "Default")
      (node (ref "R23") (pin "1") (pinfunction "1_1") (pintype "passive"))
      (node (ref "U2") (pin "36") (pinfunction "22.2_36") (pintype "passive"))
    )
    (net (code "53") (name "/22.3") (class "Default")
      (node (ref "R25") (pin "1") (pinfunction "1_1") (pintype "passive"))
      (node (ref "U2") (pin "37") (pinfunction "22.3_37") (pintype "passive"))
    )
    (net (code "54") (name "/32.4") (class "Default")
      (node (ref "P6") (pin "3") (pinfunction "3_3") (pintype "passive"))
      (node (ref "U2") (pin "32") (pinfunction "32.4_32") (pintype "passive"))
    )
    (net (code "55") (name "/33.6") (class "Default")
      (node (ref "P9") (pin "4") (pinfunction "4_4") (pintype "passive"))
      (node (ref "U2") (pin "24") (pinfunction "33.6_24") (pintype "passive"))
    )
    (net (code "56") (name "/33.7") (class "Default")
      (node (ref "P9") (pin "3") (pinfunction "3_3") (pintype "passive"))
      (node (ref "U2") (pin "25") (pinfunction "33.7_25") (pintype "passive"))
    )
    (net (code "57") (name "/33.9") (class "Default")
      (node (ref "R4") (pin "1") (pinfunction "1_1") (pintype "passive"))
      (node (ref "U2") (pin "27") (pinfunction "33.9_27") (pintype "passive"))
    )
    (net (code "58") (name "/33.10") (class "Default")
      (node (ref "R27") (pin "2") (pinfunction "2_2") (pintype "passive"))
      (node (ref "R32") (pin "2") (pinfunction "2_2") (pintype "passive"))
      (node (ref "U2") (pin "28") (pinfunction "33.10_28") (pintype "passive"))
    )
    (net (code "59") (name "/33.12") (class "Default")
      (node (ref "R14") (pin "1") (pinfunction "1_1") (pintype "passive"))
      (node (ref "U2") (pin "30") (pinfunction "33.12_30") (pintype "passive"))
    )
    (net (code "60") (name "/33.13") (class "Default")
      (node (ref "R17") (pin "1") (pinfunction "1_1") (pintype "passive"))
      (node (ref "U2") (pin "31") (pinfunction "33.13_31") (pintype "passive"))
    )
    (net (code "61") (name "/A0") (class "Default")
      (node (ref "U2") (pin "21") (pinfunction "A0_21") (pintype "passive+no_connect"))
    )
    (net (code "62") (name "/A1") (class "Default")
      (node (ref "U2") (pin "20") (pinfunction "A1_20") (pintype "passive+no_connect"))
    )
    (net (code "63") (name "/A2") (class "Default")
      (node (ref "U2") (pin "19") (pinfunction "A2_19") (pintype "passive+no_connect"))
    )
    (net (code "64") (name "/A3") (class "Default")
      (node (ref "U2") (pin "18") (pinfunction "A3_18") (pintype "passive+no_connect"))
    )
    (net (code "65") (name "/A4") (class "Default")
      (node (ref "U2") (pin "17") (pinfunction "A4_17") (pintype "passive+no_connect"))
    )
    (net (code "66") (name "/A5") (class "Default")
      (node (ref "U2") (pin "16") (pinfunction "A5_16") (pintype "passive+no_connect"))
    )
    (net (code "67") (name "/A6") (class "Default")
      (node (ref "U2") (pin "15") (pinfunction "A6_15") (pintype "passive+no_connect"))
    )
    (net (code "68") (name "/A7") (class "Default")
      (node (ref "U2") (pin "14") (pinfunction "A7_14") (pintype "passive+no_connect"))
    )
    (net (code "69") (name "/A8") (class "Default")
      (node (ref "C21") (pin "2") (pinfunction "2_2") (pintype "passive"))
      (node (ref "R33") (pin "1") (pinfunction "1_1") (pintype "passive"))
      (node (ref "R34") (pin "2") (pinfunction "2_2") (pintype "passive"))
      (node (ref "U2") (pin "13") (pinfunction "A8_13") (pintype "passive"))
    )
    (net (code "70") (name "/A10") (class "Default")
      (node (ref "P16") (pin "16") (pinfunction "16_16") (pintype "passive"))
      (node (ref "U2") (pin "12") (pinfunction "A10_12") (pintype "passive"))
    )
    (net (code "71") (name "/A11") (class "Default")
      (node (ref "P16") (pin "15") (pinfunction "15_15") (pintype "passive"))
      (node (ref "U2") (pin "11") (pinfunction "A11_11") (pintype "passive"))
    )
    (net (code "72") (name "/A12") (class "Default")
      (node (ref "P16") (pin "14") (pinfunction "14_14") (pintype "passive"))
      (node (ref "U2") (pin "10") (pinfunction "A12_10") (pintype "passive"))
    )
    (net (code "73") (name "/A13") (class "Default")
      (node (ref "P16") (pin "13") (pinfunction "13_13") (pintype "passive"))
      (node (ref "U2") (pin "9") (pinfunction "A13_9") (pintype "passive"))
    )
    (net (code "74") (name "/A16") (class "Default")
      (node (ref "P16") (pin "12") (pinfunction "12_12") (pintype "passive"))
      (node (ref "U2") (pin "8") (pinfunction "A16_8") (pintype "passive"))
    )
    (net (code "75") (name "/A17") (class "Default")
      (node (ref "P16") (pin "11") (pinfunction "11_11") (pintype "passive"))
      (node (ref "U2") (pin "7") (pinfunction "A17_7") (pintype "passive"))
    )
    (net (code "76") (name "/A20") (class "Default")
      (node (ref "P16") (pin "10") (pinfunction "10_10") (pintype "passive"))
      (node (ref "U2") (pin "6") (pinfunction "A20_6") (pintype "passive"))
    )
    (net (code "77") (name "/A21") (class "Default")
      (node (ref "P16") (pin "9") (pinfunction "9_9") (pintype "passive"))
      (node (ref "U2") (pin "5") (pinfunction "A21_5") (pintype "passive"))
    )
    (net (code "78") (name "/A24") (class "Default")
      (node (ref "P10") (pin "2") (pinfunction "2_2") (pintype "passive"))
      (node (ref "U2") (pin "122") (pinfunction "A24_122") (pintype "passive"))
    )
    (net (code "79") (name "/A25") (class "Default")
      (node (ref "U2") (pin "121") (pinfunction "A25_121") (pintype "passive"))
      (node (ref "U6") (pin "2") (pinfunction "PA13_2") (pintype "passive"))
    )
    (net (code "80") (name "/A35") (class "Default")
      (node (ref "U2") (pin "120") (pinfunction "A35_120") (pintype "passive"))
      (node (ref "U6") (pin "3") (pinfunction "PA14_3") (pintype "passive"))
    )
    (net (code "81") (name "/A36") (class "Default")
      (node (ref "U2") (pin "119") (pinfunction "A36_119") (pintype "passive"))
      (node (ref "U6") (pin "5") (pinfunction "UT_5") (pintype "passive"))
    )
    (net (code "82") (name "/DVDD") (class "Default")
      (node (ref "C32") (pin "2") (pinfunction "2_2") (pintype "passive"))
      (node (ref "U7") (pin "14") (pinfunction "VCC_14") (pintype "passive"))
      (node (ref "U8") (pin "8") (pinfunction "DVDD_8") (pintype "passive"))
    )
    (net (code "83") (name "/FB") (class "Default")
      (node (ref "R5") (pin "3") (pinfunction "BOT_3") (pintype "passive"))
      (node (ref "R7") (pin "2") (pinfunction "2_2") (pintype "passive"))
      (node (ref "U4") (pin "5") (pinfunction "FB_5") (pintype "passive"))
    )
    (net (code "84") (name "/L_A") (class "Default")
      (node (ref "P17") (pin "1") (pinfunction "1_1") (pintype "passive"))
      (node (ref "Q4") (pin "3") (pinfunction "S_3") (pintype "passive"))
      (node (ref "Q6") (pin "1") (pinfunction "D_1") (pintype "passive"))
      (node (ref "U8") (pin "23") (pinfunction "SH2_23") (pintype "passive"))
    )
    (net (code "85") (name "/L_B") (class "Default")
      (node (ref "P17") (pin "2") (pinfunction "2_2") (pintype "passive"))
      (node (ref "Q3") (pin "3") (pinfunction "S_3") (pintype "passive"))
      (node (ref "Q5") (pin "1") (pinfunction "D_1") (pintype "passive"))
      (node (ref "U8") (pin "18") (pinfunction "SH1_18") (pintype "passive"))
    )
    (net (code "86") (name "/L_EN") (class "Default")
      (node (ref "U7") (pin "6") (pinfunction "2Y_6") (pintype "passive"))
      (node (ref "U8") (pin "14") (pinfunction "EN_14") (pintype "passive"))
    )
    (net (code "87") (name "/L_EN_IN") (class "Default")
      (node (ref "P15") (pin "5") (pinfunction "5_5") (pintype "passive"))
      (node (ref "P19") (pin "5") (pinfunction "5_5") (pintype "passive"))
      (node (ref "R30") (pin "2") (pinfunction "2_2") (pintype "passive"))
      (node (ref "R44") (pin "1") (pinfunction "1_1") (pintype "passive"))
      (node (ref "U7") (pin "5") (pinfunction "2A_5") (pintype "passive"))
    )
    (net (code "88") (name "/L_PH") (class "Default")
      (node (ref "U7") (pin "3") (pinfunction "1Y_3") (pintype "passive"))
      (node (ref "U8") (pin "15") (pinfunction "PH_15") (pintype "passive"))
    )
    (net (code "89") (name "/L_PH_IN") (class "Default")
      (node (ref "P15") (pin "1") (pinfunction "1_1") (pintype "passive"))
      (node (ref "P19") (pin "1") (pinfunction "1_1") (pintype "passive"))
      (node (ref "R31") (pin "2") (pinfunction "2_2") (pintype "passive"))
      (node (ref "R43") (pin "1") (pinfunction "1_1") (pintype "passive"))
      (node (ref "U7") (pin "2") (pinfunction "1A_2") (pintype "passive"))
    )
    (net (code "90") (name "/M2") (class "Default")
      (node (ref "P15") (pin "2") (pinfunction "2_2") (pintype "passive"))
      (node (ref "P19") (pin "2") (pinfunction "2_2") (pintype "passive"))
      (node (ref "R38") (pin "1") (pinfunction "1_1") (pintype "passive"))
    )
    (net (code "91") (name "/M4") (class "Default")
      (node (ref "P15") (pin "6") (pinfunction "6_6") (pintype "passive"))
      (node (ref "P19") (pin "6") (pinfunction "6_6") (pintype "passive"))
      (node (ref "R37") (pin "1") (pinfunction "1_1") (pintype "passive"))
    )
    (net (code "92") (name "/nSLEEP") (class "Default")
      (node (ref "R39") (pin "1") (pinfunction "1_1") (pintype "passive"))
      (node (ref "S7") (pin "2") (pintype "passive"))
      (node (ref "U8") (pin "13") (pinfunction "nSLEEP_13") (pintype "passive"))
    )
    (net (code "93") (name "GND") (class "Default")
      (node (ref "C1") (pin "1") (pinfunction "1_1") (pintype "passive"))
      (node (ref "C10") (pin "1") (pinfunction "1_1") (pintype "passive"))
      (node (ref "C11") (pin "2") (pinfunction "2_2") (pintype "passive"))
      (node (ref "C12") (pin "2") (pinfunction "2_2") (pintype "passive"))
      (node (ref "C13") (pin "2") (pinfunction "2_2") (pintype "passive"))
      (node (ref "C14") (pin "2") (pinfunction "2_2") (pintype "passive"))
      (node (ref "C15") (pin "2") (pinfunction "2_2") (pintype "passive"))
      (node (ref "C16") (pin "2") (pinfunction "2_2") (pintype "passive"))
      (node (ref "C17") (pin "1") (pinfunction "1_1") (pintype "passive"))
      (node (ref "C18") (pin "2") (pinfunction "2_2") (pintype "passive"))
      (node (ref "C19") (pin "2") (pinfunction "2_2") (pintype "passive"))
      (node (ref "C2") (pin "1") (pinfunction "1_1") (pintype "passive"))
      (node (ref "C20") (pin "2") (pinfunction "2_2") (pintype "passive"))
      (node (ref "C21") (pin "1") (pinfunction "1_1") (pintype "passive"))
      (node (ref "C22") (pin "2") (pinfunction "2_2") (pintype "passive"))
      (node (ref "C29") (pin "2") (pinfunction "2_2") (pintype "passive"))
      (node (ref "C3") (pin "2") (pinfunction "2_2") (pintype "passive"))
      (node (ref "C30") (pin "2") (pinfunction "2_2") (pintype "passive"))
      (node (ref "C31") (pin "1") (pinfunction "1_1") (pintype "passive"))
      (node (ref "C32") (pin "1") (pinfunction "1_1") (pintype "passive"))
      (node (ref "C4") (pin "2") (pinfunction "2_2") (pintype "passive"))
      (node (ref "C6") (pin "1") (pinfunction "1_1") (pintype "passive"))
      (node (ref "C7") (pin "2") (pinfunction "2_2") (pintype "passive"))
      (node (ref "C8") (pin "2") (pinfunction "2_2") (pintype "passive"))
      (node (ref "C9") (pin "1") (pinfunction "1_1") (pintype "passive"))
      (node (ref "D3") (pin "A") (pinfunction "A_A") (pintype "passive"))
      (node (ref "LED1") (pin "2") (pinfunction "K_2") (pintype "passive"))
      (node (ref "LED2") (pin "2") (pinfunction "K_2") (pintype "passive"))
      (node (ref "LED3") (pin "2") (pinfunction "K_2") (pintype "passive"))
      (node (ref "LED4") (pin "2") (pinfunction "K_2") (pintype "passive"))
      (node (ref "LED5") (pin "C") (pinfunction "C_C") (pintype "passive"))
      (node (ref "LED7") (pin "C") (pinfunction "C_C") (pintype "passive"))
      (node (ref "P1") (pin "2") (pinfunction "2_2") (pintype "passive"))
      (node (ref "P10") (pin "3") (pinfunction "3_3") (pintype "passive"))
      (node (ref "P13") (pin "5") (pinfunction "5_5") (pintype "passive"))
      (node (ref "P13") (pin "6") (pinfunction "6_6") (pintype "passive"))
      (node (ref "P15") (pin "3") (pinfunction "3_3") (pintype "passive"))
      (node (ref "P15") (pin "4") (pinfunction "4_4") (pintype "passive"))
      (node (ref "P16") (pin "1") (pinfunction "1_1") (pintype "passive"))
      (node (ref "P16") (pin "3") (pinfunction "3_3") (pintype "passive"))
      (node (ref "P16") (pin "5") (pinfunction "5_5") (pintype "passive"))
      (node (ref "P16") (pin "7") (pinfunction "7_7") (pintype "passive"))
      (node (ref "P18") (pin "2") (pinfunction "2_2") (pintype "passive"))
      (node (ref "P19") (pin "3") (pinfunction "3_3") (pintype "passive"))
      (node (ref "P19") (pin "4") (pinfunction "4_4") (pintype "passive"))
      (node (ref "P2") (pin "1") (pinfunction "1_1") (pintype "passive"))
      (node (ref "P3") (pin "2") (pinfunction "2_2") (pintype "passive"))
      (node (ref "P4") (pin "3") (pinfunction "3_3") (pintype "passive"))
      (node (ref "P5") (pin "2") (pinfunction "2_2") (pintype "passive"))
      (node (ref "P6") (pin "1") (pinfunction "1_1") (pintype "passive"))
      (node (ref "P7") (pin "2") (pinfunction "2_2") (pintype "passive"))
      (node (ref "P8") (pin "2") (pinfunction "2_2") (pintype "passive"))
      (node (ref "P9") (pin "1") (pinfunction "1_1") (pintype "passive"))
      (node (ref "Q2") (pin "2") (pinfunction "E_2") (pintype "passive"))
      (node (ref "Q5") (pin "3") (pinfunction "S_3") (pintype "passive"))
      (node (ref "Q6") (pin "3") (pinfunction "S_3") (pintype "passive"))
      (node (ref "R11") (pin "1") (pinfunction "1_1") (pintype "passive"))
      (node (ref "R3") (pin "2") (pinfunction "2_2") (pintype "passive"))
      (node (ref "R32") (pin "1") (pinfunction "1_1") (pintype "passive"))
      (node (ref "R34") (pin "1") (pinfunction "1_1") (pintype "passive"))
      (node (ref "R43") (pin "2") (pinfunction "2_2") (pintype "passive"))
      (node (ref "R44") (pin "2") (pinfunction "2_2") (pintype "passive"))
      (node (ref "R7") (pin "1") (pinfunction "1_1") (pintype "passive"))
      (node (ref "S2") (pin "3") (pinfunction "B2_3") (pintype "passive"))
      (node (ref "S2") (pin "4") (pinfunction "B1_4") (pintype "passive"))
      (node (ref "S3") (pin "1") (pinfunction "1_1") (pintype "passive"))
      (node (ref "S4") (pin "1") (pinfunction "1_1") (pintype "passive"))
      (node (ref "S5") (pin "1") (pinfunction "1_1") (pintype "passive"))
      (node (ref "S6") (pin "1") (pinfunction "1_1") (pintype "passive"))
      (node (ref "U1") (pin "2") (pinfunction "GND_2") (pintype "passive"))
      (node (ref "U2") (pin "1") (pinfunction "GND_1") (pintype "passive"))
      (node (ref "U2") (pin "3") (pinfunction "GND_3") (pintype "passive"))
      (node (ref "U3") (pin "2") (pinfunction "GND_2") (pintype "passive"))
      (node (ref "U4") (pin "0") (pinfunction "GND_0") (pintype "passive"))
      (node (ref "U5") (pin "2") (pinfunction "GND_2") (pintype "passive"))
      (node (ref "U6") (pin "4") (pinfunction "GND_4") (pintype "passive"))
      (node (ref "U6") (pin "7") (pinfunction "GND_7") (pintype "passive"))
      (node (ref "U7") (pin "1") (pinfunction "1~{OE}_1") (pintype "passive"))
      (node (ref "U7") (pin "10") (pinfunction "3~{OE}_10") (pintype "passive"))
      (node (ref "U7") (pin "13") (pinfunction "4~{OE}_13") (pintype "passive"))
      (node (ref "U7") (pin "4") (pinfunction "2~{OE}_4") (pintype "passive"))
      (node (ref "U7") (pin "7") (pinfunction "GND_7") (pintype "passive"))
      (node (ref "U8") (pin "0") (pinfunction "PAD_0") (pintype "passive"))
      (node (ref "U8") (pin "16") (pinfunction "GND_16") (pintype "passive"))
      (node (ref "U8") (pin "20") (pinfunction "SN_20") (pintype "passive"))
      (node (ref "U8") (pin "21") (pinfunction "SP_21") (pintype "passive"))
      (node (ref "U8") (pin "5") (pinfunction "GND_5") (pintype "passive"))
    )
    (net (code "94") (name "Net-(B1-A)") (class "Default")
      (node (ref "B1") (pin "1") (pinfunction "A_1") (pintype "passive"))
      (node (ref "R26") (pin "1") (pinfunction "1_1") (pintype "passive"))
    )
    (net (code "95") (name "Net-(B1-B)") (class "Default")
      (node (ref "B1") (pin "2") (pinfunction "B_2") (pintype "passive"))
      (node (ref "Q2") (pin "3") (pinfunction "C_3") (pintype "passive"))
    )
    (net (code "96") (name "Net-(C5-Pad2)") (class "Default")
      (node (ref "C5") (pin "2") (pinfunction "2_2") (pintype "passive"))
      (node (ref "R6") (pin "1") (pinfunction "1_1") (pintype "passive"))
    )
    (net (code "97") (name "Net-(D1-A)") (class "Default")
      (node (ref "D1") (pin "1") (pinfunction "A_1") (pintype "passive"))
      (node (ref "R3") (pin "1") (pinfunction "1_1") (pintype "passive"))
      (node (ref "S1") (pin "3") (pinfunction "3_3") (pintype "passive"))
    )
    (net (code "98") (name "Net-(D1-K)") (class "Default")
      (node (ref "D1") (pin "2") (pinfunction "K_2") (pintype "passive"))
      (node (ref "R1") (pin "1") (pinfunction "1_1") (pintype "passive"))
      (node (ref "S1") (pin "1") (pinfunction "1_1") (pintype "passive"))
    )
    (net (code "99") (name "Net-(D2-K)") (class "Default")
      (node (ref "C17") (pin "2") (pinfunction "2_2") (pintype "passive"))
      (node (ref "C18") (pin "1") (pinfunction "1_1") (pintype "passive"))
      (node (ref "D2") (pin "2") (pinfunction "K_2") (pintype "passive"))
      (node (ref "U5") (pin "1") (pinfunction "VIN_1") (pintype "passive"))
    )
    (net (code "100") (name "Net-(LED1-A)") (class "Default")
      (node (ref "LED1") (pin "1") (pinfunction "A_1") (pintype "passive"))
      (node (ref "R2") (pin "2") (pinfunction "2_2") (pintype "passive"))
    )
    (net (code "101") (name "Net-(LED2-A)") (class "Default")
      (node (ref "LED2") (pin "1") (pinfunction "A_1") (pintype "passive"))
      (node (ref "R8") (pin "2") (pinfunction "2_2") (pintype "passive"))
    )
    (net (code "102") (name "Net-(LED3-A)") (class "Default")
      (node (ref "LED3") (pin "1") (pinfunction "A_1") (pintype "passive"))
      (node (ref "R12") (pin "1") (pinfunction "1_1") (pintype "passive"))
    )
    (net (code "103") (name "Net-(LED4-A)") (class "Default")
      (node (ref "LED4") (pin "1") (pinfunction "A_1") (pintype "passive"))
      (node (ref "R13") (pin "1") (pinfunction "1_1") (pintype "passive"))
    )
    (net (code "104") (name "Net-(LED5-PadA)") (class "Default")
      (node (ref "LED5") (pin "A") (pinfunction "A_A") (pintype "passive"))
      (node (ref "R39") (pin "2") (pinfunction "2_2") (pintype "passive"))
    )
    (net (code "105") (name "Net-(LED7-PadA)") (class "Default")
      (node (ref "LED7") (pin "A") (pinfunction "A_A") (pintype "passive"))
      (node (ref "R42") (pin "1") (pinfunction "1_1") (pintype "passive"))
    )
    (net (code "106") (name "Net-(P4-Pad1)") (class "Default")
      (node (ref "P4") (pin "1") (pinfunction "1_1") (pintype "passive"))
      (node (ref "R4") (pin "2") (pinfunction "2_2") (pintype "passive"))
    )
    (net (code "107") (name "Net-(Q1-G)") (class "Default")
      (node (ref "Q1") (pin "1") (pinfunction "G_1") (pintype "passive"))
      (node (ref "S1") (pin "2") (pinfunction "2_2") (pintype "passive"))
    )
    (net (code "108") (name "Net-(Q1-S)") (class "Default")
      (node (ref "P1") (pin "1") (pinfunction "1_1") (pintype "passive"))
      (node (ref "Q1") (pin "3") (pinfunction "S_3") (pintype "passive"))
      (node (ref "R1") (pin "2") (pinfunction "2_2") (pintype "passive"))
    )
    (net (code "109") (name "Net-(Q2-B)") (class "Default")
      (node (ref "Q2") (pin "1") (pinfunction "B_1") (pintype "passive"))
      (node (ref "R27") (pin "1") (pinfunction "1_1") (pintype "passive"))
    )
    (net (code "110") (name "Net-(Q3-G)") (class "Default")
      (node (ref "Q3") (pin "2") (pinfunction "G_2") (pintype "passive"))
      (node (ref "U8") (pin "17") (pinfunction "GH1_17") (pintype "passive"))
    )
    (net (code "111") (name "Net-(Q4-G)") (class "Default")
      (node (ref "Q4") (pin "2") (pinfunction "G_2") (pintype "passive"))
      (node (ref "U8") (pin "24") (pinfunction "GH2_24") (pintype "passive"))
    )
    (net (code "112") (name "Net-(Q5-G)") (class "Default")
      (node (ref "Q5") (pin "2") (pinfunction "G_2") (pintype "passive"))
      (node (ref "U8") (pin "19") (pinfunction "GL1_19") (pintype "passive"))
    )
    (net (code "113") (name "Net-(Q6-G)") (class "Default")
      (node (ref "Q6") (pin "2") (pinfunction "G_2") (pintype "passive"))
      (node (ref "U8") (pin "22") (pinfunction "GL2_22") (pintype "passive"))
    )
    (net (code "114") (name "Net-(R5-TAP)") (class "Default")
      (node (ref "R5") (pin "2") (pinfunction "TAP_2") (pintype "passive"))
      (node (ref "R9") (pin "2") (pinfunction "2_2") (pintype "passive"))
    )
    (net (code "115") (name "Net-(R18-Pad1)") (class "Default")
      (node (ref "R18") (pin "1") (pinfunction "1_1") (pintype "passive"))
      (node (ref "R19") (pin "2") (pinfunction "2_2") (pintype "passive"))
      (node (ref "S3") (pin "2") (pinfunction "2_2") (pintype "passive"))
    )
    (net (code "116") (name "Net-(R20-Pad1)") (class "Default")
      (node (ref "R20") (pin "1") (pinfunction "1_1") (pintype "passive"))
      (node (ref "R21") (pin "2") (pinfunction "2_2") (pintype "passive"))
      (node (ref "S4") (pin "2") (pinfunction "2_2") (pintype "passive"))
    )
    (net (code "117") (name "Net-(R22-Pad1)") (class "Default")
      (node (ref "R22") (pin "1") (pinfunction "1_1") (pintype "passive"))
      (node (ref "R23") (pin "2") (pinfunction "2_2") (pintype "passive"))
      (node (ref "S5") (pin "2") (pinfunction "2_2") (pintype "passive"))
    )
    (net (code "118") (name "Net-(R24-Pad1)") (class "Default")
      (node (ref "R24") (pin "1") (pinfunction "1_1") (pintype "passive"))
      (node (ref "R25") (pin "2") (pinfunction "2_2") (pintype "passive"))
      (node (ref "S6") (pin "2") (pinfunction "2_2") (pintype "passive"))
    )
    (net (code "119") (name "Net-(S2-A1)") (class "Default")
      (node (ref "R14") (pin "2") (pinfunction "2_2") (pintype "passive"))
      (node (ref "R15") (pin "1") (pinfunction "1_1") (pintype "passive"))
      (node (ref "S2") (pin "1") (pinfunction "A1_1") (pintype "passive"))
    )
    (net (code "120") (name "Net-(S2-A2)") (class "Default")
      (node (ref "R16") (pin "1") (pinfunction "1_1") (pintype "passive"))
      (node (ref "R17") (pin "2") (pinfunction "2_2") (pintype "passive"))
      (node (ref "S2") (pin "2") (pinfunction "A2_2") (pintype "passive"))
    )
    (net (code "121") (name "Net-(U4-BS)") (class "Default")
      (node (ref "R6") (pin "2") (pinfunction "2_2") (pintype "passive"))
      (node (ref "U4") (pin "1") (pinfunction "BS_1") (pintype "passive"))
    )
    (net (code "122") (name "Net-(U4-EN)") (class "Default")
      (node (ref "R10") (pin "2") (pinfunction "2_2") (pintype "passive"))
      (node (ref "R11") (pin "2") (pinfunction "2_2") (pintype "passive"))
      (node (ref "U4") (pin "3") (pinfunction "EN_3") (pintype "passive"))
    )
    (net (code "123") (name "Net-(U4-LX)") (class "Default")
      (node (ref "C5") (pin "1") (pinfunction "1_1") (pintype "passive"))
      (node (ref "L1") (pin "2") (pinfunction "2_2") (pintype "passive"))
      (node (ref "U4") (pin "2") (pinfunction "LX_2") (pintype "passive"))
    )
    (net (code "124") (name "Net-(U4-SS)") (class "Default")
      (node (ref "C16") (pin "1") (pinfunction "1_1") (pintype "passive"))
      (node (ref "U4") (pin "4") (pinfunction "SS_4") (pintype "passive"))
    )
    (net (code "125") (name "Net-(U4-VCC)") (class "Default")
      (node (ref "C13") (pin "1") (pinfunction "1_1") (pintype "passive"))
      (node (ref "U4") (pin "6") (pinfunction "VCC_6") (pintype "passive"))
    )
    (net (code "126") (name "Net-(U8-AVDD)") (class "Default")
      (node (ref "C31") (pin "2") (pinfunction "2_2") (pintype "passive"))
      (node (ref "U8") (pin "12") (pinfunction "IDRIVE_12") (pintype "passive"))
      (node (ref "U8") (pin "6") (pinfunction "VREF_6") (pintype "passive"))
      (node (ref "U8") (pin "7") (pinfunction "AVDD_7") (pintype "passive"))
    )
    (net (code "127") (name "Net-(U8-CPH)") (class "Default")
      (node (ref "C27") (pin "2") (pinfunction "2_2") (pintype "passive"))
      (node (ref "U8") (pin "3") (pinfunction "CPH_3") (pintype "passive"))
    )
    (net (code "128") (name "Net-(U8-CPL)") (class "Default")
      (node (ref "C27") (pin "1") (pinfunction "1_1") (pintype "passive"))
      (node (ref "U8") (pin "4") (pinfunction "CPL_4") (pintype "passive"))
    )
    (net (code "129") (name "Net-(U8-VCP)") (class "Default")
      (node (ref "C28") (pin "1") (pinfunction "1_1") (pintype "passive"))
      (node (ref "U8") (pin "2") (pinfunction "VCP_2") (pintype "passive"))
    )
    (net (code "130") (name "Net-(U8-VM)") (class "Default")
      (node (ref "C28") (pin "2") (pinfunction "2_2") (pintype "passive"))
      (node (ref "C29") (pin "1") (pinfunction "1_1") (pintype "passive"))
      (node (ref "C30") (pin "1") (pinfunction "1_1") (pintype "passive"))
      (node (ref "D4") (pin "K") (pinfunction "K_K") (pintype "passive"))
      (node (ref "U8") (pin "1") (pinfunction "VM_1") (pintype "passive"))
    )
    (net (code "131") (name "VCC3V3") (class "Default")
      (node (ref "C2") (pin "2") (pinfunction "2_2") (pintype "passive"))
      (node (ref "C4") (pin "1") (pinfunction "1_1") (pintype "passive"))
      (node (ref "D3") (pin "K") (pinfunction "K_K") (pintype "passive"))
      (node (ref "P16") (pin "2") (pinfunction "2_2") (pintype "passive"))
      (node (ref "P16") (pin "4") (pinfunction "4_4") (pintype "passive"))
      (node (ref "P16") (pin "6") (pinfunction "6_6") (pintype "passive"))
      (node (ref "P16") (pin "8") (pinfunction "8_8") (pintype "passive"))
      (node (ref "P7") (pin "4") (pinfunction "4_4") (pintype "passive"))
      (node (ref "P8") (pin "1") (pinfunction "1_1") (pintype "passive"))
      (node (ref "P9") (pin "2") (pinfunction "2_2") (pintype "passive"))
      (node (ref "R15") (pin "2") (pinfunction "2_2") (pintype "passive"))
      (node (ref "R16") (pin "2") (pinfunction "2_2") (pintype "passive"))
      (node (ref "R18") (pin "2") (pinfunction "2_2") (pintype "passive"))
      (node (ref "R2") (pin "1") (pinfunction "1_1") (pintype "passive"))
      (node (ref "R20") (pin "2") (pinfunction "2_2") (pintype "passive"))
      (node (ref "R22") (pin "2") (pinfunction "2_2") (pintype "passive"))
      (node (ref "R24") (pin "2") (pinfunction "2_2") (pintype "passive"))
      (node (ref "R26") (pin "2") (pinfunction "2_2") (pintype "passive"))
      (node (ref "R41") (pin "2") (pinfunction "2_2") (pintype "passive"))
      (node (ref "R42") (pin "2") (pinfunction "2_2") (pintype "passive"))
      (node (ref "S7") (pin "3") (pintype "passive"))
      (node (ref "U1") (pin "5") (pinfunction "OUT_5") (pintype "passive"))
    )
    (net (code "132") (name "VCC5V") (class "Default")
      (node (ref "C1") (pin "2") (pinfunction "2_2") (pintype "passive"))
      (node (ref "C11") (pin "1") (pinfunction "1_1") (pintype "passive"))
      (node (ref "C19") (pin "1") (pinfunction "1_1") (pintype "passive"))
      (node (ref "C20") (pin "1") (pinfunction "1_1") (pintype "passive"))
      (node (ref "C3") (pin "1") (pinfunction "1_1") (pintype "passive"))
      (node (ref "C9") (pin "2") (pinfunction "2_2") (pintype "passive"))
      (node (ref "P10") (pin "1") (pinfunction "1_1") (pintype "passive"))
      (node (ref "P13") (pin "7") (pinfunction "7_7") (pintype "passive"))
      (node (ref "P5") (pin "1") (pinfunction "1_1") (pintype "passive"))
      (node (ref "P6") (pin "2") (pinfunction "2_2") (pintype "passive"))
      (node (ref "R13") (pin "2") (pinfunction "2_2") (pintype "passive"))
      (node (ref "U1") (pin "1") (pinfunction "IN_1") (pintype "passive"))
      (node (ref "U1") (pin "3") (pinfunction "EN_3") (pintype "passive"))
      (node (ref "U2") (pin "2") (pinfunction "VCC_2") (pintype "passive"))
      (node (ref "U2") (pin "4") (pinfunction "VCC_4") (pintype "passive"))
      (node (ref "U3") (pin "1") (pinfunction "IN_1") (pintype "passive"))
      (node (ref "U3") (pin "3") (pinfunction "EN_3") (pintype "passive"))
      (node (ref "U5") (pin "3") (pinfunction "VOUT_3") (pintype "passive"))
      (node (ref "U6") (pin "1") (pinfunction "VCC_1") (pintype "passive"))
      (node (ref "U6") (pin "6") (pinfunction "VCC_6") (pintype "passive"))
    )
    (net (code "133") (name "VCCBAT") (class "Default")
      (node (ref "C22") (pin "1") (pinfunction "1_1") (pintype "passive"))
      (node (ref "C6") (pin "2") (pinfunction "2_2") (pintype "passive"))
      (node (ref "C7") (pin "1") (pinfunction "1_1") (pintype "passive"))
      (node (ref "C8") (pin "1") (pinfunction "1_1") (pintype "passive"))
      (node (ref "D2") (pin "1") (pinfunction "A_1") (pintype "passive"))
      (node (ref "D4") (pin "A") (pinfunction "A_A") (pintype "passive"))
      (node (ref "P18") (pin "1") (pinfunction "1_1") (pintype "passive"))
      (node (ref "P2") (pin "2") (pinfunction "2_2") (pintype "passive"))
      (node (ref "P3") (pin "1") (pinfunction "1_1") (pintype "passive"))
      (node (ref "Q1") (pin "2") (pinfunction "D_2") (pintype "passive"))
      (node (ref "Q3") (pin "1") (pinfunction "D_1") (pintype "passive"))
      (node (ref "Q4") (pin "1") (pinfunction "D_1") (pintype "passive"))
      (node (ref "R10") (pin "1") (pinfunction "1_1") (pintype "passive"))
      (node (ref "R33") (pin "2") (pinfunction "2_2") (pintype "passive"))
      (node (ref "R41") (pin "1") (pinfunction "1_1") (pintype "passive"))
      (node (ref "U4") (pin "7") (pinfunction "VIN_7") (pintype "passive"))
      (node (ref "U4") (pin "8") (pinfunction "VIN_8") (pintype "passive"))
    )
    (net (code "134") (name "VCCOP") (class "Default")
      (node (ref "C10") (pin "2") (pinfunction "2_2") (pintype "passive"))
      (node (ref "C12") (pin "1") (pinfunction "1_1") (pintype "passive"))
      (node (ref "R8") (pin "1") (pinfunction "1_1") (pintype "passive"))
      (node (ref "U3") (pin "5") (pinfunction "OUT_5") (pintype "passive"))
    )
    (net (code "135") (name "VCCSteer") (class "Default")
      (node (ref "C14") (pin "1") (pinfunction "1_1") (pintype "passive"))
      (node (ref "C15") (pin "1") (pinfunction "1_1") (pintype "passive"))
      (node (ref "L1") (pin "1") (pinfunction "1_1") (pintype "passive"))
      (node (ref "P4") (pin "2") (pinfunction "2_2") (pintype "passive"))
      (node (ref "R12") (pin "2") (pinfunction "2_2") (pintype "passive"))
      (node (ref "R9") (pin "1") (pinfunction "1_1") (pintype "passive"))
    )
    (net (code "136") (name "unconnected-(P8-Pad7)") (class "Default")
      (node (ref "P8") (pin "7") (pinfunction "7_7") (pintype "passive+no_connect"))
    )
    (net (code "137") (name "unconnected-(P8-Pad8)") (class "Default")
      (node (ref "P8") (pin "8") (pinfunction "8_8") (pintype "passive+no_connect"))
    )
    (net (code "138") (name "unconnected-(P9-Pad5)") (class "Default")
      (node (ref "P9") (pin "5") (pinfunction "5_5") (pintype "passive+no_connect"))
    )
    (net (code "139") (name "unconnected-(P9-Pad6)") (class "Default")
      (node (ref "P9") (pin "6") (pinfunction "6_6") (pintype "passive+no_connect"))
    )
    (net (code "140") (name "unconnected-(P13-Pad2)") (class "Default")
      (node (ref "P13") (pin "2") (pinfunction "2_2") (pintype "passive+no_connect"))
    )
    (net (code "141") (name "unconnected-(P13-Pad8)") (class "Default")
      (node (ref "P13") (pin "8") (pinfunction "8_8") (pintype "passive+no_connect"))
    )
    (net (code "142") (name "unconnected-(R5-TOP-Pad1)") (class "Default")
      (node (ref "R5") (pin "1") (pinfunction "TOP_1") (pintype "passive+no_connect"))
    )
    (net (code "143") (name "unconnected-(S7-Pad1)") (class "Default")
      (node (ref "S7") (pin "1") (pintype "passive+no_connect"))
    )
    (net (code "144") (name "unconnected-(U1-NC-Pad4)") (class "Default")
      (node (ref "U1") (pin "4") (pinfunction "NC_4") (pintype "passive+no_connect"))
    )
    (net (code "145") (name "unconnected-(U2-00.8-Pad107)") (class "Default")
      (node (ref "U2") (pin "107") (pinfunction "00.8_107") (pintype "passive"))
    )
    (net (code "146") (name "unconnected-(U2-00.12-Pad109)") (class "Default")
      (node (ref "U2") (pin "109") (pinfunction "00.12_109") (pintype "passive"))
    )
    (net (code "147") (name "unconnected-(U2-11.2-Pad78)") (class "Default")
      (node (ref "U2") (pin "78") (pinfunction "11.2_78") (pintype "passive"))
    )
    (net (code "148") (name "unconnected-(U2-11.3-Pad79)") (class "Default")
      (node (ref "U2") (pin "79") (pinfunction "11.3_79") (pintype "passive"))
    )
    (net (code "149") (name "unconnected-(U2-11.6-Pad80)") (class "Default")
      (node (ref "U2") (pin "80") (pinfunction "11.6_80") (pintype "passive"))
    )
    (net (code "150") (name "unconnected-(U2-14.2-Pad69)") (class "Default")
      (node (ref "U2") (pin "69") (pinfunction "14.2_69") (pintype "passive+no_connect"))
    )
    (net (code "151") (name "unconnected-(U2-14.3-Pad70)") (class "Default")
      (node (ref "U2") (pin "70") (pinfunction "14.3_70") (pintype "passive+no_connect"))
    )
    (net (code "152") (name "unconnected-(U2-14.4-Pad71)") (class "Default")
      (node (ref "U2") (pin "71") (pinfunction "14.4_71") (pintype "passive+no_connect"))
    )
    (net (code "153") (name "unconnected-(U2-14.5-Pad72)") (class "Default")
      (node (ref "U2") (pin "72") (pinfunction "14.5_72") (pintype "passive+no_connect"))
    )
    (net (code "154") (name "unconnected-(U2-14.6-Pad73)") (class "Default")
      (node (ref "U2") (pin "73") (pinfunction "14.6_73") (pintype "passive+no_connect"))
    )
    (net (code "155") (name "unconnected-(U2-15.6-Pad64)") (class "Default")
      (node (ref "U2") (pin "64") (pinfunction "15.6_64") (pintype "passive"))
    )
    (net (code "156") (name "unconnected-(U2-15.7-Pad65)") (class "Default")
      (node (ref "U2") (pin "65") (pinfunction "15.7_65") (pintype "passive"))
    )
    (net (code "157") (name "unconnected-(U2-15.8-Pad66)") (class "Default")
      (node (ref "U2") (pin "66") (pinfunction "15.8_66") (pintype "passive"))
    )
    (net (code "158") (name "unconnected-(U2-20.2-Pad45)") (class "Default")
      (node (ref "U2") (pin "45") (pinfunction "20.2_45") (pintype "passive+no_connect"))
    )
    (net (code "159") (name "unconnected-(U2-20.6-Pad49)") (class "Default")
      (node (ref "U2") (pin "49") (pinfunction "20.6_49") (pintype "passive"))
    )
    (net (code "160") (name "unconnected-(U2-20.7-Pad50)") (class "Default")
      (node (ref "U2") (pin "50") (pinfunction "20.7_50") (pintype "passive"))
    )
    (net (code "161") (name "unconnected-(U2-20.8-Pad51)") (class "Default")
      (node (ref "U2") (pin "51") (pinfunction "20.8_51") (pintype "passive"))
    )
    (net (code "162") (name "unconnected-(U2-20.9-Pad52)") (class "Default")
      (node (ref "U2") (pin "52") (pinfunction "20.9_52") (pintype "passive"))
    )
    (net (code "163") (name "unconnected-(U2-20.10-Pad53)") (class "Default")
      (node (ref "U2") (pin "53") (pinfunction "20.10_53") (pintype "passive"))
    )
    (net (code "164") (name "unconnected-(U2-21.6-Pad42)") (class "Default")
      (node (ref "U2") (pin "42") (pinfunction "21.6_42") (pintype "passive+no_connect"))
    )
    (net (code "165") (name "unconnected-(U2-21.7-Pad43)") (class "Default")
      (node (ref "U2") (pin "43") (pinfunction "21.7_43") (pintype "passive+no_connect"))
    )
    (net (code "166") (name "unconnected-(U2-23.1-Pad33)") (class "Default")
      (node (ref "U2") (pin "33") (pinfunction "23.1_33") (pintype "passive"))
    )
    (net (code "167") (name "unconnected-(U2-33.4-Pad22)") (class "Default")
      (node (ref "U2") (pin "22") (pinfunction "33.4_22") (pintype "passive"))
    )
    (net (code "168") (name "unconnected-(U2-33.5-Pad23)") (class "Default")
      (node (ref "U2") (pin "23") (pinfunction "33.5_23") (pintype "passive"))
    )
    (net (code "169") (name "unconnected-(U2-33.8-Pad26)") (class "Default")
      (node (ref "U2") (pin "26") (pinfunction "33.8_26") (pintype "passive"))
    )
    (net (code "170") (name "unconnected-(U2-33.11-Pad29)") (class "Default")
      (node (ref "U2") (pin "29") (pinfunction "33.11_29") (pintype "passive"))
    )
    (net (code "171") (name "unconnected-(U2-A37-Pad118)") (class "Default")
      (node (ref "U2") (pin "118") (pinfunction "A37_118") (pintype "passive"))
    )
    (net (code "172") (name "unconnected-(U2-A38-Pad117)") (class "Default")
      (node (ref "U2") (pin "117") (pinfunction "A38_117") (pintype "passive"))
    )
    (net (code "173") (name "unconnected-(U2-A39-Pad116)") (class "Default")
      (node (ref "U2") (pin "116") (pinfunction "A39_116") (pintype "passive"))
    )
    (net (code "174") (name "unconnected-(U2-A44-Pad115)") (class "Default")
      (node (ref "U2") (pin "115") (pinfunction "A44_115") (pintype "passive"))
    )
    (net (code "175") (name "unconnected-(U2-A45-Pad114)") (class "Default")
      (node (ref "U2") (pin "114") (pinfunction "A45_114") (pintype "passive"))
    )
    (net (code "176") (name "unconnected-(U2-A46-Pad113)") (class "Default")
      (node (ref "U2") (pin "113") (pinfunction "A46_113") (pintype "passive"))
    )
    (net (code "177") (name "unconnected-(U2-A47-Pad112)") (class "Default")
      (node (ref "U2") (pin "112") (pinfunction "A47_112") (pintype "passive"))
    )
    (net (code "178") (name "unconnected-(U2-A48-Pad111)") (class "Default")
      (node (ref "U2") (pin "111") (pinfunction "A48_111") (pintype "passive"))
    )
    (net (code "179") (name "unconnected-(U2-A49-Pad110)") (class "Default")
      (node (ref "U2") (pin "110") (pinfunction "A49_110") (pintype "passive"))
    )
    (net (code "180") (name "unconnected-(U2-ESR0-Pad48)") (class "Default")
      (node (ref "U2") (pin "48") (pinfunction "ESR0_48") (pintype "passive+no_connect"))
    )
    (net (code "181") (name "unconnected-(U2-ESR1-Pad47)") (class "Default")
      (node (ref "U2") (pin "47") (pinfunction "ESR1_47") (pintype "passive+no_connect"))
    )
    (net (code "182") (name "unconnected-(U3-NC-Pad4)") (class "Default")
      (node (ref "U3") (pin "4") (pinfunction "NC_4") (pintype "passive+no_connect"))
    )
    (net (code "183") (name "unconnected-(U7-3A-Pad9)") (class "Default")
      (node (ref "U7") (pin "9") (pinfunction "3A_9") (pintype "passive+no_connect"))
    )
    (net (code "184") (name "unconnected-(U7-3Y-Pad8)") (class "Default")
      (node (ref "U7") (pin "8") (pinfunction "3Y_8") (pintype "passive+no_connect"))
    )
    (net (code "185") (name "unconnected-(U7-4A-Pad12)") (class "Default")
      (node (ref "U7") (pin "12") (pinfunction "4A_12") (pintype "passive+no_connect"))
    )
    (net (code "186") (name "unconnected-(U7-4Y-Pad11)") (class "Default")
      (node (ref "U7") (pin "11") (pinfunction "4Y_11") (pintype "passive+no_connect"))
    )
    (net (code "187") (name "unconnected-(U8-SNSOUT-Pad10)") (class "Default")
      (node (ref "U8") (pin "10") (pinfunction "SNSOUT_10") (pintype "passive+no_connect"))
    )
    (net (code "188") (name "unconnected-(U8-SO-Pad11)") (class "Default")
      (node (ref "U8") (pin "11") (pinfunction "SO_11") (pintype "passive+no_connect"))
    )
    (net (code "189") (name "unconnected-(U8-nFAULT-Pad9)") (class "Default")
      (node (ref "U8") (pin "9") (pinfunction "nFAULT_9") (pintype "passive+no_connect"))
    )
  )
)
